# 08_MCU.net
KiCad netlist of a schematic drawn in Altium Designer
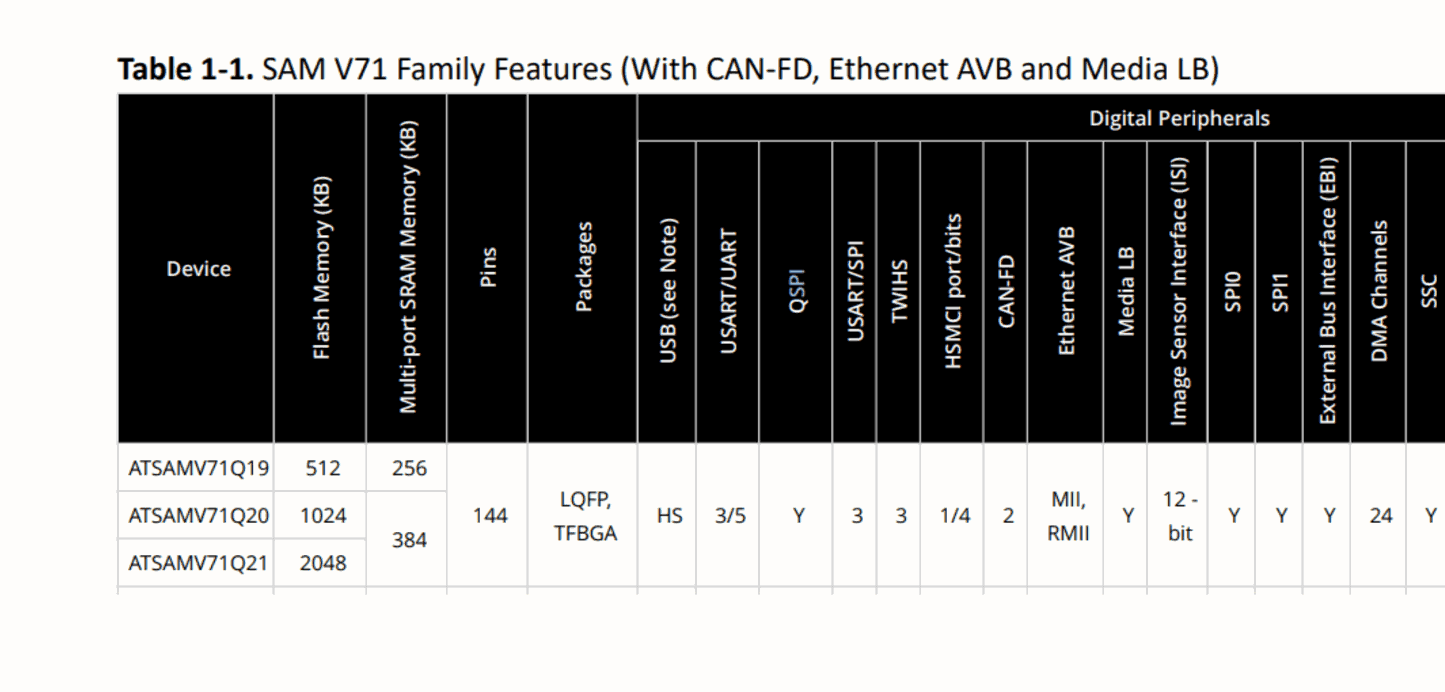
[diagram p0: 08_MCU.SchDoc, top left]
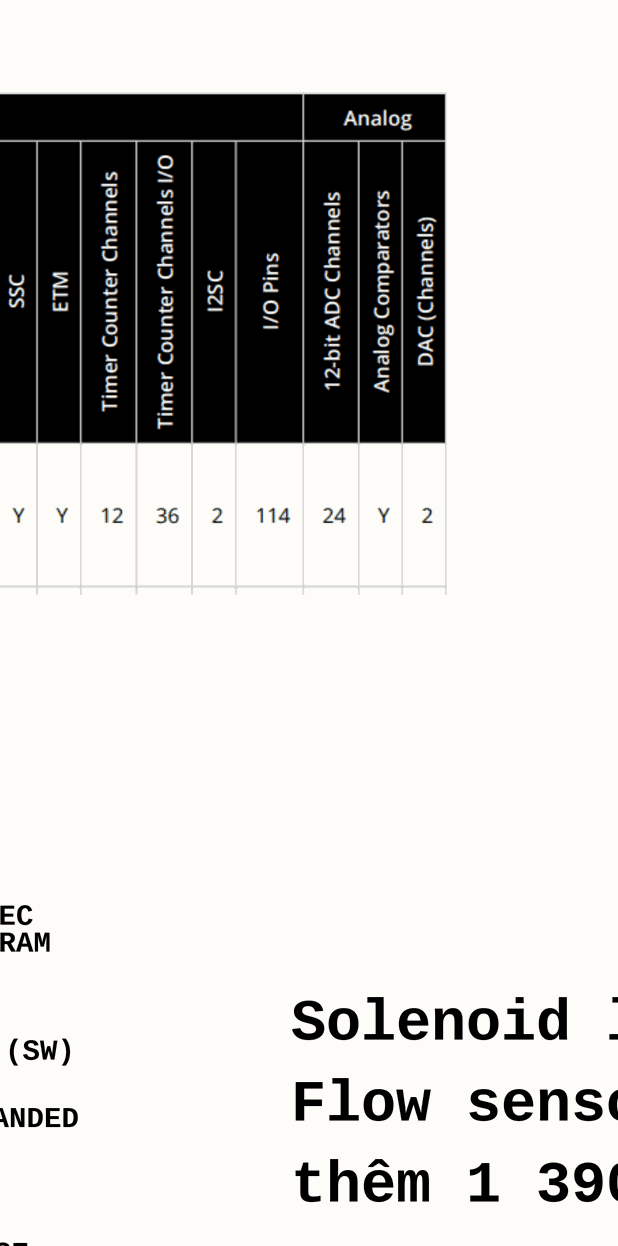
[diagram p1: 08_MCU.SchDoc, top right]
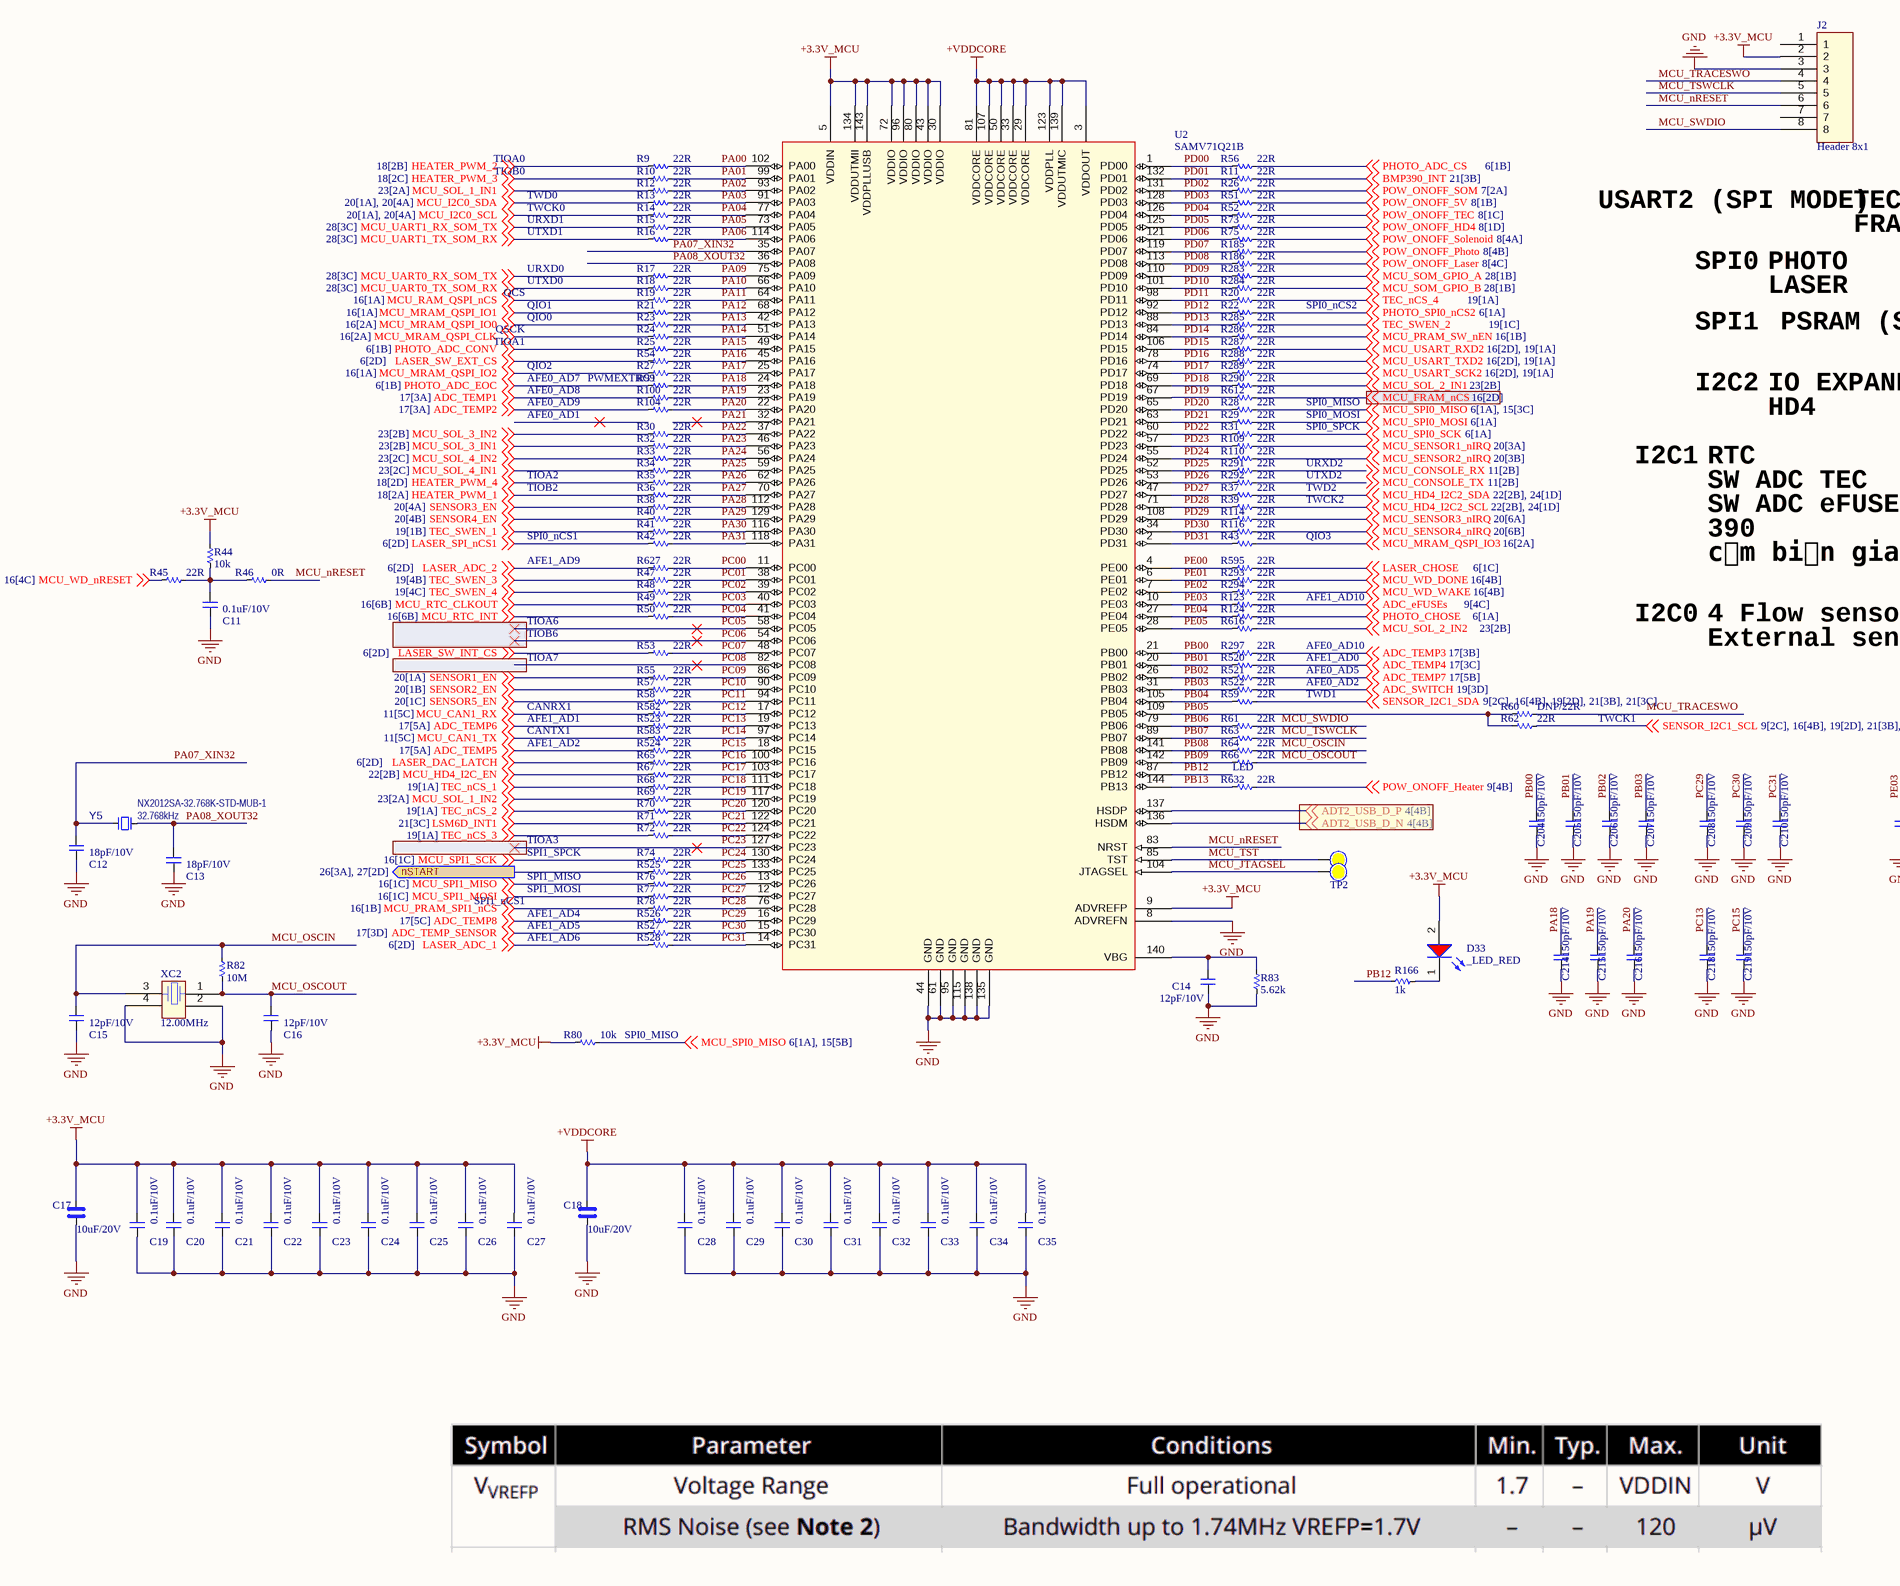
[diagram p2: 08_MCU.SchDoc, bottom left]
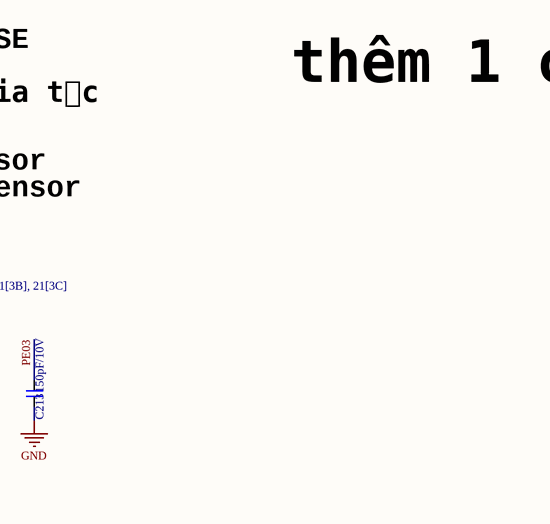
[diagram p3: 08_MCU.SchDoc, bottom right]

(export (version "E")
  (design (tool "Eeschema 10.0.6"))
  (components
    (comp (ref "C11")
      (value "0.1uF/10V")
      (footprint "CAP_C_1005X60")
      (description "CAP CHIP")
      (libsource (lib "LABLIB") (part "_CAP_C_2"))
    )
    (comp (ref "C12")
      (value "18pF/10V")
      (footprint "CAP_C_1005X60")
      (description "CAP CHIP")
      (libsource (lib "LABLIB") (part "_CAP_C_2"))
    )
    (comp (ref "C13")
      (value "18pF/10V")
      (footprint "CAP_C_1005X60")
      (description "CAP CHIP")
      (libsource (lib "LABLIB") (part "_CAP_C_2"))
    )
    (comp (ref "C14")
      (value "12pF/10V")
      (footprint "CAP_C_1005X60")
      (description "CAP CHIP")
      (libsource (lib "LABLIB") (part "_CAP_C_2"))
    )
    (comp (ref "C15")
      (value "12pF/10V")
      (footprint "CAP_C_1005X60")
      (description "CAP CHIP")
      (libsource (lib "LABLIB") (part "_CAP_C_2"))
    )
    (comp (ref "C16")
      (value "12pF/10V")
      (footprint "CAP_C_1005X60")
      (description "CAP CHIP")
      (libsource (lib "LABLIB") (part "_CAP_C_2"))
    )
    (comp (ref "C17")
      (value "10uF/20V")
      (footprint "CAP_C_2012X110")
      (description "CAP CHIP High Value")
      (libsource (lib "LABLIB") (part "_CAP_C_High_2"))
    )
    (comp (ref "C18")
      (value "10uF/20V")
      (footprint "CAP_C_2012X110")
      (description "CAP CHIP High Value")
      (libsource (lib "LABLIB") (part "_CAP_C_High_2"))
    )
    (comp (ref "C19")
      (value "0.1uF/10V")
      (footprint "CAP_C_1005X60")
      (description "CAP CHIP")
      (libsource (lib "LABLIB") (part "_CAP_C_2"))
    )
    (comp (ref "C20")
      (value "0.1uF/10V")
      (footprint "CAP_C_1005X60")
      (description "CAP CHIP")
      (libsource (lib "LABLIB") (part "_CAP_C_2"))
    )
    (comp (ref "C21")
      (value "0.1uF/10V")
      (footprint "CAP_C_1005X60")
      (description "CAP CHIP")
      (libsource (lib "LABLIB") (part "_CAP_C_2"))
    )
    (comp (ref "C22")
      (value "0.1uF/10V")
      (footprint "CAP_C_1005X60")
      (description "CAP CHIP")
      (libsource (lib "LABLIB") (part "_CAP_C_2"))
    )
    (comp (ref "C23")
      (value "0.1uF/10V")
      (footprint "CAP_C_1005X60")
      (description "CAP CHIP")
      (libsource (lib "LABLIB") (part "_CAP_C_2"))
    )
    (comp (ref "C24")
      (value "0.1uF/10V")
      (footprint "CAP_C_1005X60")
      (description "CAP CHIP")
      (libsource (lib "LABLIB") (part "_CAP_C_2"))
    )
    (comp (ref "C25")
      (value "0.1uF/10V")
      (footprint "CAP_C_1005X60")
      (description "CAP CHIP")
      (libsource (lib "LABLIB") (part "_CAP_C_2"))
    )
    (comp (ref "C26")
      (value "0.1uF/10V")
      (footprint "CAP_C_1005X60")
      (description "CAP CHIP")
      (libsource (lib "LABLIB") (part "_CAP_C_2"))
    )
    (comp (ref "C27")
      (value "0.1uF/10V")
      (footprint "CAP_C_1005X60")
      (description "CAP CHIP")
      (libsource (lib "LABLIB") (part "_CAP_C_2"))
    )
    (comp (ref "C28")
      (value "0.1uF/10V")
      (footprint "CAP_C_1005X60")
      (description "CAP CHIP")
      (libsource (lib "LABLIB") (part "_CAP_C_2"))
    )
    (comp (ref "C29")
      (value "0.1uF/10V")
      (footprint "CAP_C_1005X60")
      (description "CAP CHIP")
      (libsource (lib "LABLIB") (part "_CAP_C_2"))
    )
    (comp (ref "C30")
      (value "0.1uF/10V")
      (footprint "CAP_C_1005X60")
      (description "CAP CHIP")
      (libsource (lib "LABLIB") (part "_CAP_C_2"))
    )
    (comp (ref "C31")
      (value "0.1uF/10V")
      (footprint "CAP_C_1005X60")
      (description "CAP CHIP")
      (libsource (lib "LABLIB") (part "_CAP_C_2"))
    )
    (comp (ref "C32")
      (value "0.1uF/10V")
      (footprint "CAP_C_1005X60")
      (description "CAP CHIP")
      (libsource (lib "LABLIB") (part "_CAP_C_2"))
    )
    (comp (ref "C33")
      (value "0.1uF/10V")
      (footprint "CAP_C_1005X60")
      (description "CAP CHIP")
      (libsource (lib "LABLIB") (part "_CAP_C_2"))
    )
    (comp (ref "C34")
      (value "0.1uF/10V")
      (footprint "CAP_C_1005X60")
      (description "CAP CHIP")
      (libsource (lib "LABLIB") (part "_CAP_C_2"))
    )
    (comp (ref "C35")
      (value "0.1uF/10V")
      (footprint "CAP_C_1005X60")
      (description "CAP CHIP")
      (libsource (lib "LABLIB") (part "_CAP_C_2"))
    )
    (comp (ref "C204")
      (value "150pF/10V")
      (footprint "CAP_C_1005X60")
      (description "CAP CHIP")
      (libsource (lib "LABLIB") (part "_CAP_C_2"))
    )
    (comp (ref "C205")
      (value "150pF/10V")
      (footprint "CAP_C_1005X60")
      (description "CAP CHIP")
      (libsource (lib "LABLIB") (part "_CAP_C_2"))
    )
    (comp (ref "C206")
      (value "150pF/10V")
      (footprint "CAP_C_1005X60")
      (description "CAP CHIP")
      (libsource (lib "LABLIB") (part "_CAP_C_2"))
    )
    (comp (ref "C207")
      (value "150pF/10V")
      (footprint "CAP_C_1005X60")
      (description "CAP CHIP")
      (libsource (lib "LABLIB") (part "_CAP_C_2"))
    )
    (comp (ref "C208")
      (value "150pF/10V")
      (footprint "CAP_C_1005X60")
      (description "CAP CHIP")
      (libsource (lib "LABLIB") (part "_CAP_C_2"))
    )
    (comp (ref "C209")
      (value "150pF/10V")
      (footprint "CAP_C_1005X60")
      (description "CAP CHIP")
      (libsource (lib "LABLIB") (part "_CAP_C_2"))
    )
    (comp (ref "C210")
      (value "150pF/10V")
      (footprint "CAP_C_1005X60")
      (description "CAP CHIP")
      (libsource (lib "LABLIB") (part "_CAP_C_2"))
    )
    (comp (ref "C213")
      (value "150pF/10V")
      (footprint "CAP_C_1005X60")
      (description "CAP CHIP")
      (libsource (lib "LABLIB") (part "_CAP_C_2"))
    )
    (comp (ref "C214")
      (value "150pF/10V")
      (footprint "CAP_C_1005X60")
      (description "CAP CHIP")
      (libsource (lib "LABLIB") (part "_CAP_C_2"))
    )
    (comp (ref "C215")
      (value "150pF/10V")
      (footprint "CAP_C_1005X60")
      (description "CAP CHIP")
      (libsource (lib "LABLIB") (part "_CAP_C_2"))
    )
    (comp (ref "C216")
      (value "150pF/10V")
      (footprint "CAP_C_1005X60")
      (description "CAP CHIP")
      (libsource (lib "LABLIB") (part "_CAP_C_2"))
    )
    (comp (ref "C218")
      (value "150pF/10V")
      (footprint "CAP_C_1005X60")
      (description "CAP CHIP")
      (libsource (lib "LABLIB") (part "_CAP_C_2"))
    )
    (comp (ref "C219")
      (value "150pF/10V")
      (footprint "CAP_C_1005X60")
      (description "CAP CHIP")
      (libsource (lib "LABLIB") (part "_CAP_C_2"))
    )
    (comp (ref "D33") (value "_LED_RED") (footprint "LED_0603") (libsource (lib "LABLIB") (part "_LED_RED")))
    (comp (ref "J2")
      (value "Header 8x1")
      (footprint "Header_254P_8x1")
      (libsource (lib "LABLIB") (part "Header 8x1"))
    )
    (comp (ref "R9")
      (value "22R")
      (footprint "RES_C_1005X40")
      (description "RES")
      (libsource (lib "LABLIB") (part "_RES_B_2"))
    )
    (comp (ref "R10")
      (value "22R")
      (footprint "RES_C_1005X40")
      (description "RES")
      (libsource (lib "LABLIB") (part "_RES_B_2"))
    )
    (comp (ref "R11")
      (value "22R")
      (footprint "RES_C_1005X40")
      (description "RES")
      (libsource (lib "LABLIB") (part "_RES_B_2"))
    )
    (comp (ref "R12")
      (value "22R")
      (footprint "RES_C_1005X40")
      (description "RES")
      (libsource (lib "LABLIB") (part "_RES_B_2"))
    )
    (comp (ref "R13")
      (value "22R")
      (footprint "RES_C_1005X40")
      (description "RES")
      (libsource (lib "LABLIB") (part "_RES_B_2"))
    )
    (comp (ref "R14")
      (value "22R")
      (footprint "RES_C_1005X40")
      (description "RES")
      (libsource (lib "LABLIB") (part "_RES_B_2"))
    )
    (comp (ref "R15")
      (value "22R")
      (footprint "RES_C_1005X40")
      (description "RES")
      (libsource (lib "LABLIB") (part "_RES_B_2"))
    )
    (comp (ref "R16")
      (value "22R")
      (footprint "RES_C_1005X40")
      (description "RES")
      (libsource (lib "LABLIB") (part "_RES_B_2"))
    )
    (comp (ref "R17")
      (value "22R")
      (footprint "RES_C_1005X40")
      (description "RES")
      (libsource (lib "LABLIB") (part "_RES_B_2"))
    )
    (comp (ref "R18")
      (value "22R")
      (footprint "RES_C_1005X40")
      (description "RES")
      (libsource (lib "LABLIB") (part "_RES_B_2"))
    )
    (comp (ref "R19")
      (value "22R")
      (footprint "RES_C_1005X40")
      (description "RES")
      (libsource (lib "LABLIB") (part "_RES_B_2"))
    )
    (comp (ref "R20")
      (value "22R")
      (footprint "RES_C_1005X40")
      (description "RES")
      (libsource (lib "LABLIB") (part "_RES_B_2"))
    )
    (comp (ref "R21")
      (value "22R")
      (footprint "RES_C_1005X40")
      (description "RES")
      (libsource (lib "LABLIB") (part "_RES_B_2"))
    )
    (comp (ref "R22")
      (value "22R")
      (footprint "RES_C_1005X40")
      (description "RES")
      (libsource (lib "LABLIB") (part "_RES_B_2"))
    )
    (comp (ref "R23")
      (value "22R")
      (footprint "RES_C_1005X40")
      (description "RES")
      (libsource (lib "LABLIB") (part "_RES_B_2"))
    )
    (comp (ref "R24")
      (value "22R")
      (footprint "RES_C_1005X40")
      (description "RES")
      (libsource (lib "LABLIB") (part "_RES_B_2"))
    )
    (comp (ref "R25")
      (value "22R")
      (footprint "RES_C_1005X40")
      (description "RES")
      (libsource (lib "LABLIB") (part "_RES_B_2"))
    )
    (comp (ref "R26")
      (value "22R")
      (footprint "RES_C_1005X40")
      (description "RES")
      (libsource (lib "LABLIB") (part "_RES_B_2"))
    )
    (comp (ref "R27")
      (value "22R")
      (footprint "RES_C_1005X40")
      (description "RES")
      (libsource (lib "LABLIB") (part "_RES_B_2"))
    )
    (comp (ref "R28")
      (value "22R")
      (footprint "RES_C_1005X40")
      (description "RES")
      (libsource (lib "LABLIB") (part "_RES_B_2"))
    )
    (comp (ref "R29")
      (value "22R")
      (footprint "RES_C_1005X40")
      (description "RES")
      (libsource (lib "LABLIB") (part "_RES_B_2"))
    )
    (comp (ref "R30")
      (value "22R")
      (footprint "RES_C_1005X40")
      (description "RES")
      (libsource (lib "LABLIB") (part "_RES_B_2"))
    )
    (comp (ref "R31")
      (value "22R")
      (footprint "RES_C_1005X40")
      (description "RES")
      (libsource (lib "LABLIB") (part "_RES_B_2"))
    )
    (comp (ref "R32")
      (value "22R")
      (footprint "RES_C_1005X40")
      (description "RES")
      (libsource (lib "LABLIB") (part "_RES_B_2"))
    )
    (comp (ref "R33")
      (value "22R")
      (footprint "RES_C_1005X40")
      (description "RES")
      (libsource (lib "LABLIB") (part "_RES_B_2"))
    )
    (comp (ref "R34")
      (value "22R")
      (footprint "RES_C_1005X40")
      (description "RES")
      (libsource (lib "LABLIB") (part "_RES_B_2"))
    )
    (comp (ref "R35")
      (value "22R")
      (footprint "RES_C_1005X40")
      (description "RES")
      (libsource (lib "LABLIB") (part "_RES_B_2"))
    )
    (comp (ref "R36")
      (value "22R")
      (footprint "RES_C_1005X40")
      (description "RES")
      (libsource (lib "LABLIB") (part "_RES_B_2"))
    )
    (comp (ref "R37")
      (value "22R")
      (footprint "RES_C_1005X40")
      (description "RES")
      (libsource (lib "LABLIB") (part "_RES_B_2"))
    )
    (comp (ref "R38")
      (value "22R")
      (footprint "RES_C_1005X40")
      (description "RES")
      (libsource (lib "LABLIB") (part "_RES_B_2"))
    )
    (comp (ref "R39")
      (value "22R")
      (footprint "RES_C_1005X40")
      (description "RES")
      (libsource (lib "LABLIB") (part "_RES_B_2"))
    )
    (comp (ref "R40")
      (value "22R")
      (footprint "RES_C_1005X40")
      (description "RES")
      (libsource (lib "LABLIB") (part "_RES_B_2"))
    )
    (comp (ref "R41")
      (value "22R")
      (footprint "RES_C_1005X40")
      (description "RES")
      (libsource (lib "LABLIB") (part "_RES_B_2"))
    )
    (comp (ref "R42")
      (value "22R")
      (footprint "RES_C_1005X40")
      (description "RES")
      (libsource (lib "LABLIB") (part "_RES_B_2"))
    )
    (comp (ref "R43")
      (value "22R")
      (footprint "RES_C_1005X40")
      (description "RES")
      (libsource (lib "LABLIB") (part "_RES_B_2"))
    )
    (comp (ref "R44")
      (value "10k")
      (footprint "RES_C_1005X40")
      (description "RES")
      (libsource (lib "LABLIB") (part "_RES_B_2"))
    )
    (comp (ref "R45")
      (value "22R")
      (footprint "RES_C_1005X40")
      (description "RES")
      (libsource (lib "LABLIB") (part "_RES_B_2"))
    )
    (comp (ref "R46")
      (value "0R")
      (footprint "RES_C_1005X40")
      (description "RES")
      (libsource (lib "LABLIB") (part "_RES_B_2"))
    )
    (comp (ref "R47")
      (value "22R")
      (footprint "RES_C_1005X40")
      (description "RES")
      (libsource (lib "LABLIB") (part "_RES_B_2"))
    )
    (comp (ref "R48")
      (value "22R")
      (footprint "RES_C_1005X40")
      (description "RES")
      (libsource (lib "LABLIB") (part "_RES_B_2"))
    )
    (comp (ref "R49")
      (value "22R")
      (footprint "RES_C_1005X40")
      (description "RES")
      (libsource (lib "LABLIB") (part "_RES_B_2"))
    )
    (comp (ref "R50")
      (value "22R")
      (footprint "RES_C_1005X40")
      (description "RES")
      (libsource (lib "LABLIB") (part "_RES_B_2"))
    )
    (comp (ref "R51")
      (value "22R")
      (footprint "RES_C_1005X40")
      (description "RES")
      (libsource (lib "LABLIB") (part "_RES_B_2"))
    )
    (comp (ref "R52")
      (value "22R")
      (footprint "RES_C_1005X40")
      (description "RES")
      (libsource (lib "LABLIB") (part "_RES_B_2"))
    )
    (comp (ref "R53")
      (value "22R")
      (footprint "RES_C_1005X40")
      (description "RES")
      (libsource (lib "LABLIB") (part "_RES_B_2"))
    )
    (comp (ref "R54")
      (value "22R")
      (footprint "RES_C_1005X40")
      (description "RES")
      (libsource (lib "LABLIB") (part "_RES_B_2"))
    )
    (comp (ref "R55")
      (value "22R")
      (footprint "RES_C_1005X40")
      (description "RES")
      (libsource (lib "LABLIB") (part "_RES_B_2"))
    )
    (comp (ref "R56")
      (value "22R")
      (footprint "RES_C_1005X40")
      (description "RES")
      (libsource (lib "LABLIB") (part "_RES_B_2"))
    )
    (comp (ref "R57")
      (value "22R")
      (footprint "RES_C_1005X40")
      (description "RES")
      (libsource (lib "LABLIB") (part "_RES_B_2"))
    )
    (comp (ref "R58")
      (value "22R")
      (footprint "RES_C_1005X40")
      (description "RES")
      (libsource (lib "LABLIB") (part "_RES_B_2"))
    )
    (comp (ref "R59")
      (value "22R")
      (footprint "RES_C_1005X40")
      (description "RES")
      (libsource (lib "LABLIB") (part "_RES_B_2"))
    )
    (comp (ref "R60")
      (value "DNP/22R")
      (footprint "RES_C_1005X40")
      (description "RES")
      (libsource (lib "LABLIB") (part "_RES_B_2"))
    )
    (comp (ref "R61")
      (value "22R")
      (footprint "RES_C_1005X40")
      (description "RES")
      (libsource (lib "LABLIB") (part "_RES_B_2"))
    )
    (comp (ref "R62")
      (value "22R")
      (footprint "RES_C_1005X40")
      (description "RES")
      (libsource (lib "LABLIB") (part "_RES_B_2"))
    )
    (comp (ref "R63")
      (value "22R")
      (footprint "RES_C_1005X40")
      (description "RES")
      (libsource (lib "LABLIB") (part "_RES_B_2"))
    )
    (comp (ref "R64")
      (value "22R")
      (footprint "RES_C_1005X40")
      (description "RES")
      (libsource (lib "LABLIB") (part "_RES_B_2"))
    )
    (comp (ref "R65")
      (value "22R")
      (footprint "RES_C_1005X40")
      (description "RES")
      (libsource (lib "LABLIB") (part "_RES_B_2"))
    )
    (comp (ref "R66")
      (value "22R")
      (footprint "RES_C_1005X40")
      (description "RES")
      (libsource (lib "LABLIB") (part "_RES_B_2"))
    )
    (comp (ref "R67")
      (value "22R")
      (footprint "RES_C_1005X40")
      (description "RES")
      (libsource (lib "LABLIB") (part "_RES_B_2"))
    )
    (comp (ref "R68")
      (value "22R")
      (footprint "RES_C_1005X40")
      (description "RES")
      (libsource (lib "LABLIB") (part "_RES_B_2"))
    )
    (comp (ref "R69")
      (value "22R")
      (footprint "RES_C_1005X40")
      (description "RES")
      (libsource (lib "LABLIB") (part "_RES_B_2"))
    )
    (comp (ref "R70")
      (value "22R")
      (footprint "RES_C_1005X40")
      (description "RES")
      (libsource (lib "LABLIB") (part "_RES_B_2"))
    )
    (comp (ref "R71")
      (value "22R")
      (footprint "RES_C_1005X40")
      (description "RES")
      (libsource (lib "LABLIB") (part "_RES_B_2"))
    )
    (comp (ref "R72")
      (value "22R")
      (footprint "RES_C_1005X40")
      (description "RES")
      (libsource (lib "LABLIB") (part "_RES_B_2"))
    )
    (comp (ref "R73")
      (value "22R")
      (footprint "RES_C_1005X40")
      (description "RES")
      (libsource (lib "LABLIB") (part "_RES_B_2"))
    )
    (comp (ref "R74")
      (value "22R")
      (footprint "RES_C_1005X40")
      (description "RES")
      (libsource (lib "LABLIB") (part "_RES_B_2"))
    )
    (comp (ref "R75")
      (value "22R")
      (footprint "RES_C_1005X40")
      (description "RES")
      (libsource (lib "LABLIB") (part "_RES_B_2"))
    )
    (comp (ref "R76")
      (value "22R")
      (footprint "RES_C_1005X40")
      (description "RES")
      (libsource (lib "LABLIB") (part "_RES_B_2"))
    )
    (comp (ref "R77")
      (value "22R")
      (footprint "RES_C_1005X40")
      (description "RES")
      (libsource (lib "LABLIB") (part "_RES_B_2"))
    )
    (comp (ref "R78")
      (value "22R")
      (footprint "RES_C_1005X40")
      (description "RES")
      (libsource (lib "LABLIB") (part "_RES_B_2"))
    )
    (comp (ref "R80")
      (value "10k")
      (footprint "RES_C_1005X40")
      (description "RES")
      (libsource (lib "LABLIB") (part "_RES_B_2"))
    )
    (comp (ref "R82")
      (value "10M")
      (footprint "RES_C_1005X40")
      (description "RES")
      (libsource (lib "LABLIB") (part "_RES_B_2"))
    )
    (comp (ref "R83")
      (value "5.62k")
      (footprint "RES_C_1005X40")
      (description "RES")
      (libsource (lib "LABLIB") (part "_RES_B_2"))
    )
    (comp (ref "R99")
      (value "22R")
      (footprint "RES_C_1005X40")
      (description "RES")
      (libsource (lib "LABLIB") (part "_RES_B_2"))
    )
    (comp (ref "R100")
      (value "22R")
      (footprint "RES_C_1005X40")
      (description "RES")
      (libsource (lib "LABLIB") (part "_RES_B_2"))
    )
    (comp (ref "R104")
      (value "22R")
      (footprint "RES_C_1005X40")
      (description "RES")
      (libsource (lib "LABLIB") (part "_RES_B_2"))
    )
    (comp (ref "R109")
      (value "22R")
      (footprint "RES_C_1005X40")
      (description "RES")
      (libsource (lib "LABLIB") (part "_RES_B_2"))
    )
    (comp (ref "R110")
      (value "22R")
      (footprint "RES_C_1005X40")
      (description "RES")
      (libsource (lib "LABLIB") (part "_RES_B_2"))
    )
    (comp (ref "R114")
      (value "22R")
      (footprint "RES_C_1005X40")
      (description "RES")
      (libsource (lib "LABLIB") (part "_RES_B_2"))
    )
    (comp (ref "R116")
      (value "22R")
      (footprint "RES_C_1005X40")
      (description "RES")
      (libsource (lib "LABLIB") (part "_RES_B_2"))
    )
    (comp (ref "R123")
      (value "22R")
      (footprint "RES_C_1005X40")
      (description "RES")
      (libsource (lib "LABLIB") (part "_RES_B_2"))
    )
    (comp (ref "R124")
      (value "22R")
      (footprint "RES_C_1005X40")
      (description "RES")
      (libsource (lib "LABLIB") (part "_RES_B_2"))
    )
    (comp (ref "R166")
      (value "1k")
      (footprint "RES_C_1005X40")
      (description "RES")
      (libsource (lib "LABLIB") (part "_RES_B_2"))
    )
    (comp (ref "R185")
      (value "22R")
      (footprint "RES_C_1005X40")
      (description "RES")
      (libsource (lib "LABLIB") (part "_RES_B_2"))
    )
    (comp (ref "R186")
      (value "22R")
      (footprint "RES_C_1005X40")
      (description "RES")
      (libsource (lib "LABLIB") (part "_RES_B_2"))
    )
    (comp (ref "R283")
      (value "22R")
      (footprint "RES_C_1005X40")
      (description "RES")
      (libsource (lib "LABLIB") (part "_RES_B_2"))
    )
    (comp (ref "R284")
      (value "22R")
      (footprint "RES_C_1005X40")
      (description "RES")
      (libsource (lib "LABLIB") (part "_RES_B_2"))
    )
    (comp (ref "R285")
      (value "22R")
      (footprint "RES_C_1005X40")
      (description "RES")
      (libsource (lib "LABLIB") (part "_RES_B_2"))
    )
    (comp (ref "R286")
      (value "22R")
      (footprint "RES_C_1005X40")
      (description "RES")
      (libsource (lib "LABLIB") (part "_RES_B_2"))
    )
    (comp (ref "R287")
      (value "22R")
      (footprint "RES_C_1005X40")
      (description "RES")
      (libsource (lib "LABLIB") (part "_RES_B_2"))
    )
    (comp (ref "R288")
      (value "22R")
      (footprint "RES_C_1005X40")
      (description "RES")
      (libsource (lib "LABLIB") (part "_RES_B_2"))
    )
    (comp (ref "R289")
      (value "22R")
      (footprint "RES_C_1005X40")
      (description "RES")
      (libsource (lib "LABLIB") (part "_RES_B_2"))
    )
    (comp (ref "R290")
      (value "22R")
      (footprint "RES_C_1005X40")
      (description "RES")
      (libsource (lib "LABLIB") (part "_RES_B_2"))
    )
    (comp (ref "R291")
      (value "22R")
      (footprint "RES_C_1005X40")
      (description "RES")
      (libsource (lib "LABLIB") (part "_RES_B_2"))
    )
    (comp (ref "R292")
      (value "22R")
      (footprint "RES_C_1005X40")
      (description "RES")
      (libsource (lib "LABLIB") (part "_RES_B_2"))
    )
    (comp (ref "R293")
      (value "22R")
      (footprint "RES_C_1005X40")
      (description "RES")
      (libsource (lib "LABLIB") (part "_RES_B_2"))
    )
    (comp (ref "R294")
      (value "22R")
      (footprint "RES_C_1005X40")
      (description "RES")
      (libsource (lib "LABLIB") (part "_RES_B_2"))
    )
    (comp (ref "R297")
      (value "22R")
      (footprint "RES_C_1005X40")
      (description "RES")
      (libsource (lib "LABLIB") (part "_RES_B_2"))
    )
    (comp (ref "R520")
      (value "22R")
      (footprint "RES_C_1005X40")
      (description "RES")
      (libsource (lib "LABLIB") (part "_RES_B_2"))
    )
    (comp (ref "R521")
      (value "22R")
      (footprint "RES_C_1005X40")
      (description "RES")
      (libsource (lib "LABLIB") (part "_RES_B_2"))
    )
    (comp (ref "R522")
      (value "22R")
      (footprint "RES_C_1005X40")
      (description "RES")
      (libsource (lib "LABLIB") (part "_RES_B_2"))
    )
    (comp (ref "R523")
      (value "22R")
      (footprint "RES_C_1005X40")
      (description "RES")
      (libsource (lib "LABLIB") (part "_RES_B_2"))
    )
    (comp (ref "R524")
      (value "22R")
      (footprint "RES_C_1005X40")
      (description "RES")
      (libsource (lib "LABLIB") (part "_RES_B_2"))
    )
    (comp (ref "R525")
      (value "22R")
      (footprint "RES_C_1005X40")
      (description "RES")
      (libsource (lib "LABLIB") (part "_RES_B_2"))
    )
    (comp (ref "R526")
      (value "22R")
      (footprint "RES_C_1005X40")
      (description "RES")
      (libsource (lib "LABLIB") (part "_RES_B_2"))
    )
    (comp (ref "R527")
      (value "22R")
      (footprint "RES_C_1005X40")
      (description "RES")
      (libsource (lib "LABLIB") (part "_RES_B_2"))
    )
    (comp (ref "R528")
      (value "22R")
      (footprint "RES_C_1005X40")
      (description "RES")
      (libsource (lib "LABLIB") (part "_RES_B_2"))
    )
    (comp (ref "R582")
      (value "22R")
      (footprint "RES_C_1005X40")
      (description "RES")
      (libsource (lib "LABLIB") (part "_RES_B_2"))
    )
    (comp (ref "R583")
      (value "22R")
      (footprint "RES_C_1005X40")
      (description "RES")
      (libsource (lib "LABLIB") (part "_RES_B_2"))
    )
    (comp (ref "R595")
      (value "22R")
      (footprint "RES_C_1005X40")
      (description "RES")
      (libsource (lib "LABLIB") (part "_RES_B_2"))
    )
    (comp (ref "R612")
      (value "22R")
      (footprint "RES_C_1005X40")
      (description "RES")
      (libsource (lib "LABLIB") (part "_RES_B_2"))
    )
    (comp (ref "R616")
      (value "22R")
      (footprint "RES_C_1005X40")
      (description "RES")
      (libsource (lib "LABLIB") (part "_RES_B_2"))
    )
    (comp (ref "R627")
      (value "22R")
      (footprint "RES_C_1005X40")
      (description "RES")
      (libsource (lib "LABLIB") (part "_RES_B_2"))
    )
    (comp (ref "R632")
      (value "22R")
      (footprint "RES_C_1005X40")
      (description "RES")
      (libsource (lib "LABLIB") (part "_RES_B_2"))
    )
    (comp (ref "TP1")
      (value "~")
      (footprint "Testpoint_TH_D130H80")
      (description "Test Point")
      (libsource (lib "LABLIB") (part "Test Point"))
    )
    (comp (ref "TP2")
      (value "~")
      (footprint "Testpoint_TH_D130H80")
      (description "Test Point")
      (libsource (lib "LABLIB") (part "Test Point"))
    )
    (comp (ref "U2")
      (value "SAMV71Q21B")
      (footprint "AP6-00118")
      (description "SAM 32-bit ARM Cortex-M* RISC MCU, SAMV71B Series, QFP144")
      (fields (field (name "MANUFACTURER") "MICROCHIP") (field (name "MPN") "ATSAMV71Q21B-AAB"))
      (libsource (lib "AltiumDbLib") (part "SAMV7_LQFP144"))
    )
    (comp (ref "XC2")
      (value "12.00MHz")
      (footprint "AP7-00039")
      (description "Fox FQ5032B 12.0MHz SMD crystal 738B-12")
      (fields (field (name "TOLERANCE") "Â±30ppm") (field (name "MANUFACTURER") "Fox  Electronics"))
      (libsource (lib "AltiumDbLib") (part "CRYSTAL1324"))
    )
    (comp (ref "Y5")
      (value "32.768kHz")
      (footprint "CRYSTAL_NX2012SA")
      (description "Crystal")
      (fields
        (field (name "TOLERANCE") "±20ppm")
        (field (name "MANUFACTURER PART NUMBER 1") "NX2012SA-32.768K-STD-MUB-1")
        (field (name "Comment") "Crystal 2 Pins")
        (field (name "OWNER") "Jamus Griego")
      )
      (libsource (lib "MCHP-CDB") (part "Crystal 2 Pins"))
    )
  )
  (nets
    (net (code "1") (name "+3.3V_MCU") (class "Default")
      (node (ref "C17") (pin "1") (pinfunction "1_1") (pintype "passive"))
      (node (ref "C19") (pin "2") (pinfunction "2_2") (pintype "passive"))
      (node (ref "C20") (pin "2") (pinfunction "2_2") (pintype "passive"))
      (node (ref "C21") (pin "2") (pinfunction "2_2") (pintype "passive"))
      (node (ref "C22") (pin "2") (pinfunction "2_2") (pintype "passive"))
      (node (ref "C23") (pin "2") (pinfunction "2_2") (pintype "passive"))
      (node (ref "C24") (pin "2") (pinfunction "2_2") (pintype "passive"))
      (node (ref "C25") (pin "2") (pinfunction "2_2") (pintype "passive"))
      (node (ref "C26") (pin "2") (pinfunction "2_2") (pintype "passive"))
      (node (ref "C27") (pin "2") (pinfunction "2_2") (pintype "passive"))
      (node (ref "D33") (pin "2") (pinfunction "A_2") (pintype "passive"))
      (node (ref "J2") (pin "2") (pinfunction "2_2") (pintype "passive"))
      (node (ref "R44") (pin "2") (pinfunction "2_2") (pintype "passive"))
      (node (ref "R80") (pin "2") (pinfunction "2_2") (pintype "passive"))
      (node (ref "U2") (pin "134") (pinfunction "VDDUTMII_134") (pintype "power_in"))
      (node (ref "U2") (pin "143") (pinfunction "VDDPLLUSB_143") (pintype "power_in"))
      (node (ref "U2") (pin "30") (pinfunction "VDDIO_30") (pintype "power_in"))
      (node (ref "U2") (pin "43") (pinfunction "VDDIO_43") (pintype "power_in"))
      (node (ref "U2") (pin "5") (pinfunction "VDDIN_5") (pintype "power_in"))
      (node (ref "U2") (pin "72") (pinfunction "VDDIO_72") (pintype "power_in"))
      (node (ref "U2") (pin "80") (pinfunction "VDDIO_80") (pintype "power_in"))
      (node (ref "U2") (pin "9") (pinfunction "ADVREFP_9") (pintype "power_in"))
      (node (ref "U2") (pin "96") (pinfunction "VDDIO_96") (pintype "power_in"))
    )
    (net (code "2") (name "+VDDCORE") (class "Default")
      (node (ref "C18") (pin "1") (pinfunction "1_1") (pintype "passive"))
      (node (ref "C28") (pin "2") (pinfunction "2_2") (pintype "passive"))
      (node (ref "C29") (pin "2") (pinfunction "2_2") (pintype "passive"))
      (node (ref "C30") (pin "2") (pinfunction "2_2") (pintype "passive"))
      (node (ref "C31") (pin "2") (pinfunction "2_2") (pintype "passive"))
      (node (ref "C32") (pin "2") (pinfunction "2_2") (pintype "passive"))
      (node (ref "C33") (pin "2") (pinfunction "2_2") (pintype "passive"))
      (node (ref "C34") (pin "2") (pinfunction "2_2") (pintype "passive"))
      (node (ref "C35") (pin "2") (pinfunction "2_2") (pintype "passive"))
      (node (ref "U2") (pin "107") (pinfunction "VDDCORE_107") (pintype "power_in"))
      (node (ref "U2") (pin "123") (pinfunction "VDDPLL_123") (pintype "power_in"))
      (node (ref "U2") (pin "139") (pinfunction "VDDUTMIC_139") (pintype "power_in"))
      (node (ref "U2") (pin "29") (pinfunction "VDDCORE_29") (pintype "power_in"))
      (node (ref "U2") (pin "3") (pinfunction "VDDOUT_3") (pintype "power_in"))
      (node (ref "U2") (pin "33") (pinfunction "VDDCORE_33") (pintype "power_in"))
      (node (ref "U2") (pin "50") (pinfunction "VDDCORE_50") (pintype "power_in"))
      (node (ref "U2") (pin "81") (pinfunction "VDDCORE_81") (pintype "power_in"))
    )
    (net (code "3") (name "/MCU_JTAGSEL") (class "Default")
      (node (ref "TP2") (pin "1") (pinfunction "1_1") (pintype "passive"))
      (node (ref "U2") (pin "104") (pinfunction "JTAGSEL_104") (pintype "input"))
    )
    (net (code "4") (name "/MCU_OSCIN") (class "Default")
      (node (ref "C15") (pin "2") (pinfunction "2_2") (pintype "passive"))
      (node (ref "R64") (pin "1") (pinfunction "1_1") (pintype "passive"))
      (node (ref "R82") (pin "2") (pinfunction "2_2") (pintype "passive"))
      (node (ref "XC2") (pin "3") (pinfunction "3_3") (pintype "passive"))
    )
    (net (code "5") (name "/MCU_OSCOUT") (class "Default")
      (node (ref "C16") (pin "2") (pinfunction "2_2") (pintype "passive"))
      (node (ref "R66") (pin "1") (pinfunction "1_1") (pintype "passive"))
      (node (ref "R82") (pin "1") (pinfunction "1_1") (pintype "passive"))
      (node (ref "XC2") (pin "1") (pinfunction "1_1") (pintype "passive"))
    )
    (net (code "6") (name "/MCU_SWDIO") (class "Default")
      (node (ref "J2") (pin "8") (pinfunction "8_8") (pintype "passive"))
      (node (ref "R61") (pin "1") (pinfunction "1_1") (pintype "passive"))
    )
    (net (code "7") (name "/MCU_TRACESWO") (class "Default")
      (node (ref "J2") (pin "4") (pinfunction "4_4") (pintype "passive"))
      (node (ref "R60") (pin "1") (pinfunction "1_1") (pintype "passive"))
    )
    (net (code "8") (name "/MCU_TST") (class "Default")
      (node (ref "TP1") (pin "1") (pinfunction "1_1") (pintype "passive"))
      (node (ref "U2") (pin "85") (pinfunction "TST_85") (pintype "input"))
    )
    (net (code "9") (name "/MCU_TSWCLK") (class "Default")
      (node (ref "J2") (pin "5") (pinfunction "5_5") (pintype "passive"))
      (node (ref "R63") (pin "1") (pinfunction "1_1") (pintype "passive"))
    )
    (net (code "10") (name "/MCU_nRESET") (class "Default")
      (node (ref "J2") (pin "6") (pinfunction "6_6") (pintype "passive"))
      (node (ref "R46") (pin "1") (pinfunction "1_1") (pintype "passive"))
      (node (ref "U2") (pin "83") (pinfunction "NRST_83") (pintype "input"))
    )
    (net (code "11") (name "/PA00") (class "Default")
      (node (ref "R9") (pin "1") (pinfunction "1_1") (pintype "passive"))
      (node (ref "U2") (pin "102") (pinfunction "PA00_102") (pintype "bidirectional"))
    )
    (net (code "12") (name "/PA01") (class "Default")
      (node (ref "R10") (pin "1") (pinfunction "1_1") (pintype "passive"))
      (node (ref "U2") (pin "99") (pinfunction "PA01_99") (pintype "bidirectional"))
    )
    (net (code "13") (name "/PA02") (class "Default")
      (node (ref "R12") (pin "1") (pinfunction "1_1") (pintype "passive"))
      (node (ref "U2") (pin "93") (pinfunction "PA02_93") (pintype "bidirectional"))
    )
    (net (code "14") (name "/PA03") (class "Default")
      (node (ref "R13") (pin "1") (pinfunction "1_1") (pintype "passive"))
      (node (ref "U2") (pin "91") (pinfunction "PA03_91") (pintype "bidirectional"))
    )
    (net (code "15") (name "/PA04") (class "Default")
      (node (ref "R14") (pin "1") (pinfunction "1_1") (pintype "passive"))
      (node (ref "U2") (pin "77") (pinfunction "PA04_77") (pintype "bidirectional"))
    )
    (net (code "16") (name "/PA05") (class "Default")
      (node (ref "R15") (pin "1") (pinfunction "1_1") (pintype "passive"))
      (node (ref "U2") (pin "73") (pinfunction "PA05_73") (pintype "bidirectional"))
    )
    (net (code "17") (name "/PA06") (class "Default")
      (node (ref "R16") (pin "1") (pinfunction "1_1") (pintype "passive"))
      (node (ref "U2") (pin "114") (pinfunction "PA06_114") (pintype "bidirectional"))
    )
    (net (code "18") (name "/PA07_XIN32") (class "Default")
      (node (ref "C12") (pin "2") (pinfunction "2_2") (pintype "passive"))
      (node (ref "U2") (pin "35") (pinfunction "PA07_35") (pintype "bidirectional"))
      (node (ref "Y5") (pin "2") (pinfunction "Osc2_2") (pintype "passive"))
    )
    (net (code "19") (name "/PA08_XOUT32") (class "Default")
      (node (ref "C13") (pin "2") (pinfunction "2_2") (pintype "passive"))
      (node (ref "U2") (pin "36") (pinfunction "PA08_36") (pintype "bidirectional"))
      (node (ref "Y5") (pin "1") (pinfunction "Osc1_1") (pintype "passive"))
    )
    (net (code "20") (name "/PA09") (class "Default")
      (node (ref "R17") (pin "1") (pinfunction "1_1") (pintype "passive"))
      (node (ref "U2") (pin "75") (pinfunction "PA09_75") (pintype "bidirectional"))
    )
    (net (code "21") (name "/PA10") (class "Default")
      (node (ref "R18") (pin "1") (pinfunction "1_1") (pintype "passive"))
      (node (ref "U2") (pin "66") (pinfunction "PA10_66") (pintype "bidirectional"))
    )
    (net (code "22") (name "/PA11") (class "Default")
      (node (ref "R19") (pin "1") (pinfunction "1_1") (pintype "passive"))
      (node (ref "U2") (pin "64") (pinfunction "PA11_64") (pintype "bidirectional"))
    )
    (net (code "23") (name "/PA12") (class "Default")
      (node (ref "R21") (pin "1") (pinfunction "1_1") (pintype "passive"))
      (node (ref "U2") (pin "68") (pinfunction "PA12_68") (pintype "bidirectional"))
    )
    (net (code "24") (name "/PA13") (class "Default")
      (node (ref "R23") (pin "1") (pinfunction "1_1") (pintype "passive"))
      (node (ref "U2") (pin "42") (pinfunction "PA13_42") (pintype "bidirectional"))
    )
    (net (code "25") (name "/PA14") (class "Default")
      (node (ref "R24") (pin "1") (pinfunction "1_1") (pintype "passive"))
      (node (ref "U2") (pin "51") (pinfunction "PA14_51") (pintype "bidirectional"))
    )
    (net (code "26") (name "/PA15") (class "Default")
      (node (ref "R25") (pin "1") (pinfunction "1_1") (pintype "passive"))
      (node (ref "U2") (pin "49") (pinfunction "PA15_49") (pintype "bidirectional"))
    )
    (net (code "27") (name "/PA16") (class "Default")
      (node (ref "R54") (pin "1") (pinfunction "1_1") (pintype "passive"))
      (node (ref "U2") (pin "45") (pinfunction "PA16_45") (pintype "bidirectional"))
    )
    (net (code "28") (name "/PA17") (class "Default")
      (node (ref "R27") (pin "1") (pinfunction "1_1") (pintype "passive"))
      (node (ref "U2") (pin "25") (pinfunction "PA17_25") (pintype "bidirectional"))
    )
    (net (code "29") (name "/PA18") (class "Default")
      (node (ref "C214") (pin "2") (pinfunction "2_2") (pintype "passive"))
      (node (ref "R99") (pin "1") (pinfunction "1_1") (pintype "passive"))
      (node (ref "U2") (pin "24") (pinfunction "PA18_24") (pintype "bidirectional"))
    )
    (net (code "30") (name "/PA19") (class "Default")
      (node (ref "C215") (pin "2") (pinfunction "2_2") (pintype "passive"))
      (node (ref "R100") (pin "1") (pinfunction "1_1") (pintype "passive"))
      (node (ref "U2") (pin "23") (pinfunction "PA19_23") (pintype "bidirectional"))
    )
    (net (code "31") (name "/PA20") (class "Default")
      (node (ref "C216") (pin "2") (pinfunction "2_2") (pintype "passive"))
      (node (ref "R104") (pin "1") (pinfunction "1_1") (pintype "passive"))
      (node (ref "U2") (pin "22") (pinfunction "PA20_22") (pintype "bidirectional"))
    )
    (net (code "32") (name "/PA21") (class "Default")
      (node (ref "U2") (pin "32") (pinfunction "PA21_32") (pintype "bidirectional"))
    )
    (net (code "33") (name "/PA22") (class "Default")
      (node (ref "R30") (pin "1") (pinfunction "1_1") (pintype "passive"))
      (node (ref "U2") (pin "37") (pinfunction "PA22_37") (pintype "bidirectional"))
    )
    (net (code "34") (name "/PA23") (class "Default")
      (node (ref "R32") (pin "1") (pinfunction "1_1") (pintype "passive"))
      (node (ref "U2") (pin "46") (pinfunction "PA23_46") (pintype "bidirectional"))
    )
    (net (code "35") (name "/PA24") (class "Default")
      (node (ref "R33") (pin "1") (pinfunction "1_1") (pintype "passive"))
      (node (ref "U2") (pin "56") (pinfunction "PA24_56") (pintype "bidirectional"))
    )
    (net (code "36") (name "/PA25") (class "Default")
      (node (ref "R34") (pin "1") (pinfunction "1_1") (pintype "passive"))
      (node (ref "U2") (pin "59") (pinfunction "PA25_59") (pintype "bidirectional"))
    )
    (net (code "37") (name "/PA26") (class "Default")
      (node (ref "R35") (pin "1") (pinfunction "1_1") (pintype "passive"))
      (node (ref "U2") (pin "62") (pinfunction "PA26_62") (pintype "bidirectional"))
    )
    (net (code "38") (name "/PA27") (class "Default")
      (node (ref "R36") (pin "1") (pinfunction "1_1") (pintype "passive"))
      (node (ref "U2") (pin "70") (pinfunction "PA27_70") (pintype "bidirectional"))
    )
    (net (code "39") (name "/PA28") (class "Default")
      (node (ref "R38") (pin "1") (pinfunction "1_1") (pintype "passive"))
      (node (ref "U2") (pin "112") (pinfunction "PA28_112") (pintype "bidirectional"))
    )
    (net (code "40") (name "/PA29") (class "Default")
      (node (ref "R40") (pin "1") (pinfunction "1_1") (pintype "passive"))
      (node (ref "U2") (pin "129") (pinfunction "PA29_129") (pintype "bidirectional"))
    )
    (net (code "41") (name "/PA30") (class "Default")
      (node (ref "R41") (pin "1") (pinfunction "1_1") (pintype "passive"))
      (node (ref "U2") (pin "116") (pinfunction "PA30_116") (pintype "bidirectional"))
    )
    (net (code "42") (name "/PA31") (class "Default")
      (node (ref "R42") (pin "1") (pinfunction "1_1") (pintype "passive"))
      (node (ref "U2") (pin "118") (pinfunction "PA31_118") (pintype "bidirectional"))
    )
    (net (code "43") (name "/PB00") (class "Default")
      (node (ref "C204") (pin "2") (pinfunction "2_2") (pintype "passive"))
      (node (ref "R297") (pin "2") (pinfunction "2_2") (pintype "passive"))
      (node (ref "U2") (pin "21") (pinfunction "PB00_21") (pintype "bidirectional"))
    )
    (net (code "44") (name "/PB01") (class "Default")
      (node (ref "C205") (pin "2") (pinfunction "2_2") (pintype "passive"))
      (node (ref "R520") (pin "2") (pinfunction "2_2") (pintype "passive"))
      (node (ref "U2") (pin "20") (pinfunction "PB01_20") (pintype "bidirectional"))
    )
    (net (code "45") (name "/PB02") (class "Default")
      (node (ref "C206") (pin "2") (pinfunction "2_2") (pintype "passive"))
      (node (ref "R521") (pin "2") (pinfunction "2_2") (pintype "passive"))
      (node (ref "U2") (pin "26") (pinfunction "PB02_26") (pintype "bidirectional"))
    )
    (net (code "46") (name "/PB03") (class "Default")
      (node (ref "C207") (pin "2") (pinfunction "2_2") (pintype "passive"))
      (node (ref "R522") (pin "2") (pinfunction "2_2") (pintype "passive"))
      (node (ref "U2") (pin "31") (pinfunction "PB03_31") (pintype "bidirectional"))
    )
    (net (code "47") (name "/PB04") (class "Default")
      (node (ref "R59") (pin "2") (pinfunction "2_2") (pintype "passive"))
      (node (ref "U2") (pin "105") (pinfunction "PB04_105") (pintype "bidirectional"))
    )
    (net (code "48") (name "/PB05") (class "Default")
      (node (ref "R60") (pin "2") (pinfunction "2_2") (pintype "passive"))
      (node (ref "R62") (pin "2") (pinfunction "2_2") (pintype "passive"))
      (node (ref "U2") (pin "109") (pinfunction "PB05_109") (pintype "bidirectional"))
    )
    (net (code "49") (name "/PB06") (class "Default")
      (node (ref "R61") (pin "2") (pinfunction "2_2") (pintype "passive"))
      (node (ref "U2") (pin "79") (pinfunction "PB06_79") (pintype "bidirectional"))
    )
    (net (code "50") (name "/PB07") (class "Default")
      (node (ref "R63") (pin "2") (pinfunction "2_2") (pintype "passive"))
      (node (ref "U2") (pin "89") (pinfunction "PB07_89") (pintype "bidirectional"))
    )
    (net (code "51") (name "/PB08") (class "Default")
      (node (ref "R64") (pin "2") (pinfunction "2_2") (pintype "passive"))
      (node (ref "U2") (pin "141") (pinfunction "PB08_141") (pintype "bidirectional"))
    )
    (net (code "52") (name "/PB09") (class "Default")
      (node (ref "R66") (pin "2") (pinfunction "2_2") (pintype "passive"))
      (node (ref "U2") (pin "142") (pinfunction "PB09_142") (pintype "bidirectional"))
    )
    (net (code "53") (name "/PB12") (class "Default")
      (node (ref "R166") (pin "1") (pinfunction "1_1") (pintype "passive"))
      (node (ref "U2") (pin "87") (pinfunction "PB12_87") (pintype "bidirectional"))
    )
    (net (code "54") (name "/PB13") (class "Default")
      (node (ref "R632") (pin "2") (pinfunction "2_2") (pintype "passive"))
      (node (ref "U2") (pin "144") (pinfunction "PB13_144") (pintype "bidirectional"))
    )
    (net (code "55") (name "/PC00") (class "Default")
      (node (ref "R627") (pin "1") (pinfunction "1_1") (pintype "passive"))
      (node (ref "U2") (pin "11") (pinfunction "PC00_11") (pintype "bidirectional"))
    )
    (net (code "56") (name "/PC01") (class "Default")
      (node (ref "R47") (pin "1") (pinfunction "1_1") (pintype "passive"))
      (node (ref "U2") (pin "38") (pinfunction "PC01_38") (pintype "bidirectional"))
    )
    (net (code "57") (name "/PC02") (class "Default")
      (node (ref "R48") (pin "1") (pinfunction "1_1") (pintype "passive"))
      (node (ref "U2") (pin "39") (pinfunction "PC02_39") (pintype "bidirectional"))
    )
    (net (code "58") (name "/PC03") (class "Default")
      (node (ref "R49") (pin "1") (pinfunction "1_1") (pintype "passive"))
      (node (ref "U2") (pin "40") (pinfunction "PC03_40") (pintype "bidirectional"))
    )
    (net (code "59") (name "/PC04") (class "Default")
      (node (ref "R50") (pin "1") (pinfunction "1_1") (pintype "passive"))
      (node (ref "U2") (pin "41") (pinfunction "PC04_41") (pintype "bidirectional"))
    )
    (net (code "60") (name "/PC05") (class "Default")
      (node (ref "U2") (pin "58") (pinfunction "PC05_58") (pintype "bidirectional+no_connect"))
    )
    (net (code "61") (name "/PC06") (class "Default")
      (node (ref "U2") (pin "54") (pinfunction "PC06_54") (pintype "bidirectional+no_connect"))
    )
    (net (code "62") (name "/PC07") (class "Default")
      (node (ref "R53") (pin "1") (pinfunction "1_1") (pintype "passive"))
      (node (ref "U2") (pin "48") (pinfunction "PC07_48") (pintype "bidirectional"))
    )
    (net (code "63") (name "/PC08") (class "Default")
      (node (ref "U2") (pin "82") (pinfunction "PC08_82") (pintype "bidirectional"))
    )
    (net (code "64") (name "/PC09") (class "Default")
      (node (ref "R55") (pin "1") (pinfunction "1_1") (pintype "passive"))
      (node (ref "U2") (pin "86") (pinfunction "PC09_86") (pintype "bidirectional"))
    )
    (net (code "65") (name "/PC10") (class "Default")
      (node (ref "R57") (pin "1") (pinfunction "1_1") (pintype "passive"))
      (node (ref "U2") (pin "90") (pinfunction "PC10_90") (pintype "bidirectional"))
    )
    (net (code "66") (name "/PC11") (class "Default")
      (node (ref "R58") (pin "1") (pinfunction "1_1") (pintype "passive"))
      (node (ref "U2") (pin "94") (pinfunction "PC11_94") (pintype "bidirectional"))
    )
    (net (code "67") (name "/PC12") (class "Default")
      (node (ref "R582") (pin "1") (pinfunction "1_1") (pintype "passive"))
      (node (ref "U2") (pin "17") (pinfunction "PC12_17") (pintype "bidirectional"))
    )
    (net (code "68") (name "/PC13") (class "Default")
      (node (ref "C218") (pin "2") (pinfunction "2_2") (pintype "passive"))
      (node (ref "R523") (pin "1") (pinfunction "1_1") (pintype "passive"))
      (node (ref "U2") (pin "19") (pinfunction "PC13_19") (pintype "bidirectional"))
    )
    (net (code "69") (name "/PC14") (class "Default")
      (node (ref "R583") (pin "1") (pinfunction "1_1") (pintype "passive"))
      (node (ref "U2") (pin "97") (pinfunction "PC14_97") (pintype "bidirectional"))
    )
    (net (code "70") (name "/PC15") (class "Default")
      (node (ref "C219") (pin "2") (pinfunction "2_2") (pintype "passive"))
      (node (ref "R524") (pin "1") (pinfunction "1_1") (pintype "passive"))
      (node (ref "U2") (pin "18") (pinfunction "PC15_18") (pintype "bidirectional"))
    )
    (net (code "71") (name "/PC16") (class "Default")
      (node (ref "R65") (pin "1") (pinfunction "1_1") (pintype "passive"))
      (node (ref "U2") (pin "100") (pinfunction "PC16_100") (pintype "bidirectional"))
    )
    (net (code "72") (name "/PC17") (class "Default")
      (node (ref "R67") (pin "1") (pinfunction "1_1") (pintype "passive"))
      (node (ref "U2") (pin "103") (pinfunction "PC17_103") (pintype "bidirectional"))
    )
    (net (code "73") (name "/PC18") (class "Default")
      (node (ref "R68") (pin "1") (pinfunction "1_1") (pintype "passive"))
      (node (ref "U2") (pin "111") (pinfunction "PC18_111") (pintype "bidirectional"))
    )
    (net (code "74") (name "/PC19") (class "Default")
      (node (ref "R69") (pin "1") (pinfunction "1_1") (pintype "passive"))
      (node (ref "U2") (pin "117") (pinfunction "PC19_117") (pintype "bidirectional"))
    )
    (net (code "75") (name "/PC20") (class "Default")
      (node (ref "R70") (pin "1") (pinfunction "1_1") (pintype "passive"))
      (node (ref "U2") (pin "120") (pinfunction "PC20_120") (pintype "bidirectional"))
    )
    (net (code "76") (name "/PC21") (class "Default")
      (node (ref "R71") (pin "1") (pinfunction "1_1") (pintype "passive"))
      (node (ref "U2") (pin "122") (pinfunction "PC21_122") (pintype "bidirectional"))
    )
    (net (code "77") (name "/PC22") (class "Default")
      (node (ref "R72") (pin "1") (pinfunction "1_1") (pintype "passive"))
      (node (ref "U2") (pin "124") (pinfunction "PC22_124") (pintype "bidirectional"))
    )
    (net (code "78") (name "/PC23") (class "Default")
      (node (ref "U2") (pin "127") (pinfunction "PC23_127") (pintype "bidirectional+no_connect"))
    )
    (net (code "79") (name "/PC24") (class "Default")
      (node (ref "R74") (pin "1") (pinfunction "1_1") (pintype "passive"))
      (node (ref "U2") (pin "130") (pinfunction "PC24_130") (pintype "bidirectional"))
    )
    (net (code "80") (name "/PC25") (class "Default")
      (node (ref "R525") (pin "1") (pinfunction "1_1") (pintype "passive"))
      (node (ref "U2") (pin "133") (pinfunction "PC25_133") (pintype "bidirectional"))
    )
    (net (code "81") (name "/PC26") (class "Default")
      (node (ref "R76") (pin "1") (pinfunction "1_1") (pintype "passive"))
      (node (ref "U2") (pin "13") (pinfunction "PC26_13") (pintype "bidirectional"))
    )
    (net (code "82") (name "/PC27") (class "Default")
      (node (ref "R77") (pin "1") (pinfunction "1_1") (pintype "passive"))
      (node (ref "U2") (pin "12") (pinfunction "PC27_12") (pintype "bidirectional"))
    )
    (net (code "83") (name "/PC28") (class "Default")
      (node (ref "R78") (pin "1") (pinfunction "1_1") (pintype "passive"))
      (node (ref "U2") (pin "76") (pinfunction "PC28_76") (pintype "bidirectional"))
    )
    (net (code "84") (name "/PC29") (class "Default")
      (node (ref "C208") (pin "2") (pinfunction "2_2") (pintype "passive"))
      (node (ref "R526") (pin "1") (pinfunction "1_1") (pintype "passive"))
      (node (ref "U2") (pin "16") (pinfunction "PC29_16") (pintype "bidirectional"))
    )
    (net (code "85") (name "/PC30") (class "Default")
      (node (ref "C209") (pin "2") (pinfunction "2_2") (pintype "passive"))
      (node (ref "R527") (pin "1") (pinfunction "1_1") (pintype "passive"))
      (node (ref "U2") (pin "15") (pinfunction "PC30_15") (pintype "bidirectional"))
    )
    (net (code "86") (name "/PC31") (class "Default")
      (node (ref "C210") (pin "2") (pinfunction "2_2") (pintype "passive"))
      (node (ref "R528") (pin "1") (pinfunction "1_1") (pintype "passive"))
      (node (ref "U2") (pin "14") (pinfunction "PC31_14") (pintype "bidirectional"))
    )
    (net (code "87") (name "/PD00") (class "Default")
      (node (ref "R56") (pin "2") (pinfunction "2_2") (pintype "passive"))
      (node (ref "U2") (pin "1") (pinfunction "PD00_1") (pintype "bidirectional"))
    )
    (net (code "88") (name "/PD01") (class "Default")
      (node (ref "R11") (pin "2") (pinfunction "2_2") (pintype "passive"))
      (node (ref "U2") (pin "132") (pinfunction "PD01_132") (pintype "bidirectional"))
    )
    (net (code "89") (name "/PD02") (class "Default")
      (node (ref "R26") (pin "2") (pinfunction "2_2") (pintype "passive"))
      (node (ref "U2") (pin "131") (pinfunction "PD02_131") (pintype "bidirectional"))
    )
    (net (code "90") (name "/PD03") (class "Default")
      (node (ref "R51") (pin "2") (pinfunction "2_2") (pintype "passive"))
      (node (ref "U2") (pin "128") (pinfunction "PD03_128") (pintype "bidirectional"))
    )
    (net (code "91") (name "/PD04") (class "Default")
      (node (ref "R52") (pin "2") (pinfunction "2_2") (pintype "passive"))
      (node (ref "U2") (pin "126") (pinfunction "PD04_126") (pintype "bidirectional"))
    )
    (net (code "92") (name "/PD05") (class "Default")
      (node (ref "R73") (pin "2") (pinfunction "2_2") (pintype "passive"))
      (node (ref "U2") (pin "125") (pinfunction "PD05_125") (pintype "bidirectional"))
    )
    (net (code "93") (name "/PD06") (class "Default")
      (node (ref "R75") (pin "2") (pinfunction "2_2") (pintype "passive"))
      (node (ref "U2") (pin "121") (pinfunction "PD06_121") (pintype "bidirectional"))
    )
    (net (code "94") (name "/PD07") (class "Default")
      (node (ref "R185") (pin "2") (pinfunction "2_2") (pintype "passive"))
      (node (ref "U2") (pin "119") (pinfunction "PD07_119") (pintype "bidirectional"))
    )
    (net (code "95") (name "/PD08") (class "Default")
      (node (ref "R186") (pin "2") (pinfunction "2_2") (pintype "passive"))
      (node (ref "U2") (pin "113") (pinfunction "PD08_113") (pintype "bidirectional"))
    )
    (net (code "96") (name "/PD09") (class "Default")
      (node (ref "R283") (pin "2") (pinfunction "2_2") (pintype "passive"))
      (node (ref "U2") (pin "110") (pinfunction "PD09_110") (pintype "bidirectional"))
    )
    (net (code "97") (name "/PD10") (class "Default")
      (node (ref "R284") (pin "2") (pinfunction "2_2") (pintype "passive"))
      (node (ref "U2") (pin "101") (pinfunction "PD10_101") (pintype "bidirectional"))
    )
    (net (code "98") (name "/PD11") (class "Default")
      (node (ref "R20") (pin "2") (pinfunction "2_2") (pintype "passive"))
      (node (ref "U2") (pin "98") (pinfunction "PD11_98") (pintype "bidirectional"))
    )
    (net (code "99") (name "/PD12") (class "Default")
      (node (ref "R22") (pin "2") (pinfunction "2_2") (pintype "passive"))
      (node (ref "U2") (pin "92") (pinfunction "PD12_92") (pintype "bidirectional"))
    )
    (net (code "100") (name "/PD13") (class "Default")
      (node (ref "R285") (pin "2") (pinfunction "2_2") (pintype "passive"))
      (node (ref "U2") (pin "88") (pinfunction "PD13_88") (pintype "bidirectional"))
    )
    (net (code "101") (name "/PD14") (class "Default")
      (node (ref "R286") (pin "2") (pinfunction "2_2") (pintype "passive"))
      (node (ref "U2") (pin "84") (pinfunction "PD14_84") (pintype "bidirectional"))
    )
    (net (code "102") (name "/PD15") (class "Default")
      (node (ref "R287") (pin "2") (pinfunction "2_2") (pintype "passive"))
      (node (ref "U2") (pin "106") (pinfunction "PD15_106") (pintype "bidirectional"))
    )
    (net (code "103") (name "/PD16") (class "Default")
      (node (ref "R288") (pin "2") (pinfunction "2_2") (pintype "passive"))
      (node (ref "U2") (pin "78") (pinfunction "PD16_78") (pintype "bidirectional"))
    )
    (net (code "104") (name "/PD17") (class "Default")
      (node (ref "R289") (pin "2") (pinfunction "2_2") (pintype "passive"))
      (node (ref "U2") (pin "74") (pinfunction "PD17_74") (pintype "bidirectional"))
    )
    (net (code "105") (name "/PD18") (class "Default")
      (node (ref "R290") (pin "2") (pinfunction "2_2") (pintype "passive"))
      (node (ref "U2") (pin "69") (pinfunction "PD18_69") (pintype "bidirectional"))
    )
    (net (code "106") (name "/PD19") (class "Default")
      (node (ref "R612") (pin "2") (pinfunction "2_2") (pintype "passive"))
      (node (ref "U2") (pin "67") (pinfunction "PD19_67") (pintype "bidirectional"))
    )
    (net (code "107") (name "/PD20") (class "Default")
      (node (ref "R28") (pin "2") (pinfunction "2_2") (pintype "passive"))
      (node (ref "U2") (pin "65") (pinfunction "PD20_65") (pintype "bidirectional"))
    )
    (net (code "108") (name "/PD21") (class "Default")
      (node (ref "R29") (pin "2") (pinfunction "2_2") (pintype "passive"))
      (node (ref "U2") (pin "63") (pinfunction "PD21_63") (pintype "bidirectional"))
    )
    (net (code "109") (name "/PD22") (class "Default")
      (node (ref "R31") (pin "2") (pinfunction "2_2") (pintype "passive"))
      (node (ref "U2") (pin "60") (pinfunction "PD22_60") (pintype "bidirectional"))
    )
    (net (code "110") (name "/PD23") (class "Default")
      (node (ref "R109") (pin "2") (pinfunction "2_2") (pintype "passive"))
      (node (ref "U2") (pin "57") (pinfunction "PD23_57") (pintype "bidirectional"))
    )
    (net (code "111") (name "/PD24") (class "Default")
      (node (ref "R110") (pin "2") (pinfunction "2_2") (pintype "passive"))
      (node (ref "U2") (pin "55") (pinfunction "PD24_55") (pintype "bidirectional"))
    )
    (net (code "112") (name "/PD25") (class "Default")
      (node (ref "R291") (pin "2") (pinfunction "2_2") (pintype "passive"))
      (node (ref "U2") (pin "52") (pinfunction "PD25_52") (pintype "bidirectional"))
    )
    (net (code "113") (name "/PD26") (class "Default")
      (node (ref "R292") (pin "2") (pinfunction "2_2") (pintype "passive"))
      (node (ref "U2") (pin "53") (pinfunction "PD26_53") (pintype "bidirectional"))
    )
    (net (code "114") (name "/PD27") (class "Default")
      (node (ref "R37") (pin "2") (pinfunction "2_2") (pintype "passive"))
      (node (ref "U2") (pin "47") (pinfunction "PD27_47") (pintype "bidirectional"))
    )
    (net (code "115") (name "/PD28") (class "Default")
      (node (ref "R39") (pin "2") (pinfunction "2_2") (pintype "passive"))
      (node (ref "U2") (pin "71") (pinfunction "PD28_71") (pintype "bidirectional"))
    )
    (net (code "116") (name "/PD29") (class "Default")
      (node (ref "R114") (pin "2") (pinfunction "2_2") (pintype "passive"))
      (node (ref "U2") (pin "108") (pinfunction "PD29_108") (pintype "bidirectional"))
    )
    (net (code "117") (name "/PD30") (class "Default")
      (node (ref "R116") (pin "2") (pinfunction "2_2") (pintype "passive"))
      (node (ref "U2") (pin "34") (pinfunction "PD30_34") (pintype "bidirectional"))
    )
    (net (code "118") (name "/PD31") (class "Default")
      (node (ref "R43") (pin "2") (pinfunction "2_2") (pintype "passive"))
      (node (ref "U2") (pin "2") (pinfunction "PD31_2") (pintype "bidirectional"))
    )
    (net (code "119") (name "/PE00") (class "Default")
      (node (ref "R595") (pin "2") (pinfunction "2_2") (pintype "passive"))
      (node (ref "U2") (pin "4") (pinfunction "PE00_4") (pintype "bidirectional"))
    )
    (net (code "120") (name "/PE01") (class "Default")
      (node (ref "R293") (pin "2") (pinfunction "2_2") (pintype "passive"))
      (node (ref "U2") (pin "6") (pinfunction "PE01_6") (pintype "bidirectional"))
    )
    (net (code "121") (name "/PE02") (class "Default")
      (node (ref "R294") (pin "2") (pinfunction "2_2") (pintype "passive"))
      (node (ref "U2") (pin "7") (pinfunction "PE02_7") (pintype "bidirectional"))
    )
    (net (code "122") (name "/PE03") (class "Default")
      (node (ref "C213") (pin "2") (pinfunction "2_2") (pintype "passive"))
      (node (ref "R123") (pin "2") (pinfunction "2_2") (pintype "passive"))
      (node (ref "U2") (pin "10") (pinfunction "PE03_10") (pintype "bidirectional"))
    )
    (net (code "123") (name "/PE04") (class "Default")
      (node (ref "R124") (pin "2") (pinfunction "2_2") (pintype "passive"))
      (node (ref "U2") (pin "27") (pinfunction "PE04_27") (pintype "bidirectional"))
    )
    (net (code "124") (name "/PE05") (class "Default")
      (node (ref "R616") (pin "2") (pinfunction "2_2") (pintype "passive"))
      (node (ref "U2") (pin "28") (pinfunction "PE05_28") (pintype "bidirectional"))
    )
    (net (code "125") (name "/nSTART") (class "Default")
      (node (ref "R525") (pin "2") (pinfunction "2_2") (pintype "passive"))
    )
    (net (code "126") (name "ADC_SWITCH") (class "Default")
      (node (ref "R522") (pin "1") (pinfunction "1_1") (pintype "passive"))
    )
    (net (code "127") (name "ADC_TEMP1") (class "Default")
      (node (ref "R100") (pin "2") (pinfunction "2_2") (pintype "passive"))
    )
    (net (code "128") (name "ADC_TEMP2") (class "Default")
      (node (ref "R104") (pin "2") (pinfunction "2_2") (pintype "passive"))
    )
    (net (code "129") (name "ADC_TEMP3") (class "Default")
      (node (ref "R297") (pin "1") (pinfunction "1_1") (pintype "passive"))
    )
    (net (code "130") (name "ADC_TEMP4") (class "Default")
      (node (ref "R520") (pin "1") (pinfunction "1_1") (pintype "passive"))
    )
    (net (code "131") (name "ADC_TEMP5") (class "Default")
      (node (ref "R524") (pin "2") (pinfunction "2_2") (pintype "passive"))
    )
    (net (code "132") (name "ADC_TEMP6") (class "Default")
      (node (ref "R523") (pin "2") (pinfunction "2_2") (pintype "passive"))
    )
    (net (code "133") (name "ADC_TEMP7") (class "Default")
      (node (ref "R521") (pin "1") (pinfunction "1_1") (pintype "passive"))
    )
    (net (code "134") (name "ADC_TEMP8") (class "Default")
      (node (ref "R526") (pin "2") (pinfunction "2_2") (pintype "passive"))
    )
    (net (code "135") (name "ADC_TEMP_SENSOR") (class "Default")
      (node (ref "R527") (pin "2") (pinfunction "2_2") (pintype "passive"))
    )
    (net (code "136") (name "ADC_eFUSEs") (class "Default")
      (node (ref "R123") (pin "1") (pinfunction "1_1") (pintype "passive"))
    )
    (net (code "137") (name "ADT2_USB_D_N") (class "Default")
      (node (ref "U2") (pin "136") (pinfunction "HSDM_136") (pintype "bidirectional"))
    )
    (net (code "138") (name "ADT2_USB_D_P") (class "Default")
      (node (ref "U2") (pin "137") (pinfunction "HSDP_137") (pintype "bidirectional"))
    )
    (net (code "139") (name "BMP390_INT") (class "Default")
      (node (ref "R11") (pin "1") (pinfunction "1_1") (pintype "passive"))
    )
    (net (code "140") (name "GND") (class "Default")
      (node (ref "C11") (pin "1") (pinfunction "1_1") (pintype "passive"))
      (node (ref "C12") (pin "1") (pinfunction "1_1") (pintype "passive"))
      (node (ref "C13") (pin "1") (pinfunction "1_1") (pintype "passive"))
      (node (ref "C14") (pin "1") (pinfunction "1_1") (pintype "passive"))
      (node (ref "C15") (pin "1") (pinfunction "1_1") (pintype "passive"))
      (node (ref "C16") (pin "1") (pinfunction "1_1") (pintype "passive"))
      (node (ref "C17") (pin "2") (pinfunction "2_2") (pintype "passive"))
      (node (ref "C18") (pin "2") (pinfunction "2_2") (pintype "passive"))
      (node (ref "C19") (pin "1") (pinfunction "1_1") (pintype "passive"))
      (node (ref "C20") (pin "1") (pinfunction "1_1") (pintype "passive"))
      (node (ref "C204") (pin "1") (pinfunction "1_1") (pintype "passive"))
      (node (ref "C205") (pin "1") (pinfunction "1_1") (pintype "passive"))
      (node (ref "C206") (pin "1") (pinfunction "1_1") (pintype "passive"))
      (node (ref "C207") (pin "1") (pinfunction "1_1") (pintype "passive"))
      (node (ref "C208") (pin "1") (pinfunction "1_1") (pintype "passive"))
      (node (ref "C209") (pin "1") (pinfunction "1_1") (pintype "passive"))
      (node (ref "C21") (pin "1") (pinfunction "1_1") (pintype "passive"))
      (node (ref "C210") (pin "1") (pinfunction "1_1") (pintype "passive"))
      (node (ref "C213") (pin "1") (pinfunction "1_1") (pintype "passive"))
      (node (ref "C214") (pin "1") (pinfunction "1_1") (pintype "passive"))
      (node (ref "C215") (pin "1") (pinfunction "1_1") (pintype "passive"))
      (node (ref "C216") (pin "1") (pinfunction "1_1") (pintype "passive"))
      (node (ref "C218") (pin "1") (pinfunction "1_1") (pintype "passive"))
      (node (ref "C219") (pin "1") (pinfunction "1_1") (pintype "passive"))
      (node (ref "C22") (pin "1") (pinfunction "1_1") (pintype "passive"))
      (node (ref "C23") (pin "1") (pinfunction "1_1") (pintype "passive"))
      (node (ref "C24") (pin "1") (pinfunction "1_1") (pintype "passive"))
      (node (ref "C25") (pin "1") (pinfunction "1_1") (pintype "passive"))
      (node (ref "C26") (pin "1") (pinfunction "1_1") (pintype "passive"))
      (node (ref "C27") (pin "1") (pinfunction "1_1") (pintype "passive"))
      (node (ref "C28") (pin "1") (pinfunction "1_1") (pintype "passive"))
      (node (ref "C29") (pin "1") (pinfunction "1_1") (pintype "passive"))
      (node (ref "C30") (pin "1") (pinfunction "1_1") (pintype "passive"))
      (node (ref "C31") (pin "1") (pinfunction "1_1") (pintype "passive"))
      (node (ref "C32") (pin "1") (pinfunction "1_1") (pintype "passive"))
      (node (ref "C33") (pin "1") (pinfunction "1_1") (pintype "passive"))
      (node (ref "C34") (pin "1") (pinfunction "1_1") (pintype "passive"))
      (node (ref "C35") (pin "1") (pinfunction "1_1") (pintype "passive"))
      (node (ref "J2") (pin "3") (pinfunction "3_3") (pintype "passive"))
      (node (ref "R83") (pin "1") (pinfunction "1_1") (pintype "passive"))
      (node (ref "U2") (pin "115") (pinfunction "GND_115") (pintype "power_in"))
      (node (ref "U2") (pin "135") (pinfunction "GND_135") (pintype "power_in"))
      (node (ref "U2") (pin "138") (pinfunction "GND_138") (pintype "power_in"))
      (node (ref "U2") (pin "44") (pinfunction "GND_44") (pintype "power_in"))
      (node (ref "U2") (pin "61") (pinfunction "GND_61") (pintype "power_in"))
      (node (ref "U2") (pin "8") (pinfunction "ADVREFN_8") (pintype "power_in"))
      (node (ref "U2") (pin "95") (pinfunction "GND_95") (pintype "power_in"))
      (node (ref "XC2") (pin "2") (pinfunction "2_2") (pintype "passive"))
      (node (ref "XC2") (pin "4") (pinfunction "4_4") (pintype "passive"))
    )
    (net (code "141") (name "HEATER_PWM_1") (class "Default")
      (node (ref "R36") (pin "2") (pinfunction "2_2") (pintype "passive"))
    )
    (net (code "142") (name "HEATER_PWM_2") (class "Default")
      (node (ref "R9") (pin "2") (pinfunction "2_2") (pintype "passive"))
    )
    (net (code "143") (name "HEATER_PWM_3") (class "Default")
      (node (ref "R10") (pin "2") (pinfunction "2_2") (pintype "passive"))
    )
    (net (code "144") (name "HEATER_PWM_4") (class "Default")
      (node (ref "R35") (pin "2") (pinfunction "2_2") (pintype "passive"))
    )
    (net (code "145") (name "LASER_ADC_1") (class "Default")
      (node (ref "R528") (pin "2") (pinfunction "2_2") (pintype "passive"))
    )
    (net (code "146") (name "LASER_ADC_2") (class "Default")
      (node (ref "R627") (pin "2") (pinfunction "2_2") (pintype "passive"))
    )
    (net (code "147") (name "LASER_CHOSE") (class "Default")
      (node (ref "R595") (pin "1") (pinfunction "1_1") (pintype "passive"))
    )
    (net (code "148") (name "LASER_DAC_LATCH") (class "Default")
      (node (ref "R65") (pin "2") (pinfunction "2_2") (pintype "passive"))
    )
    (net (code "149") (name "LASER_SPI_nCS1") (class "Default")
      (node (ref "R42") (pin "2") (pinfunction "2_2") (pintype "passive"))
    )
    (net (code "150") (name "LASER_SW_EXT_CS") (class "Default")
      (node (ref "R54") (pin "2") (pinfunction "2_2") (pintype "passive"))
    )
    (net (code "151") (name "LASER_SW_INT_CS") (class "Default")
      (node (ref "R53") (pin "2") (pinfunction "2_2") (pintype "passive"))
    )
    (net (code "152") (name "LSM6D_INT1") (class "Default")
      (node (ref "R71") (pin "2") (pinfunction "2_2") (pintype "passive"))
    )
    (net (code "153") (name "MCU_CAN1_RX") (class "Default")
      (node (ref "R582") (pin "2") (pinfunction "2_2") (pintype "passive"))
    )
    (net (code "154") (name "MCU_CAN1_TX") (class "Default")
      (node (ref "R583") (pin "2") (pinfunction "2_2") (pintype "passive"))
    )
    (net (code "155") (name "MCU_CONSOLE_RX") (class "Default")
      (node (ref "R291") (pin "1") (pinfunction "1_1") (pintype "passive"))
    )
    (net (code "156") (name "MCU_CONSOLE_TX") (class "Default")
      (node (ref "R292") (pin "1") (pinfunction "1_1") (pintype "passive"))
    )
    (net (code "157") (name "MCU_FRAM_nCS") (class "Default")
      (node (ref "R612") (pin "1") (pinfunction "1_1") (pintype "passive"))
    )
    (net (code "158") (name "MCU_HD4_I2C2_SCL") (class "Default")
      (node (ref "R39") (pin "1") (pinfunction "1_1") (pintype "passive"))
    )
    (net (code "159") (name "MCU_HD4_I2C2_SDA") (class "Default")
      (node (ref "R37") (pin "1") (pinfunction "1_1") (pintype "passive"))
    )
    (net (code "160") (name "MCU_HD4_I2C_EN") (class "Default")
      (node (ref "R67") (pin "2") (pinfunction "2_2") (pintype "passive"))
    )
    (net (code "161") (name "MCU_I2C0_SCL") (class "Default")
      (node (ref "R14") (pin "2") (pinfunction "2_2") (pintype "passive"))
    )
    (net (code "162") (name "MCU_I2C0_SDA") (class "Default")
      (node (ref "R13") (pin "2") (pinfunction "2_2") (pintype "passive"))
    )
    (net (code "163") (name "MCU_MRAM_QSPI_CLK") (class "Default")
      (node (ref "R24") (pin "2") (pinfunction "2_2") (pintype "passive"))
    )
    (net (code "164") (name "MCU_MRAM_QSPI_IO0") (class "Default")
      (node (ref "R23") (pin "2") (pinfunction "2_2") (pintype "passive"))
    )
    (net (code "165") (name "MCU_MRAM_QSPI_IO1") (class "Default")
      (node (ref "R21") (pin "2") (pinfunction "2_2") (pintype "passive"))
    )
    (net (code "166") (name "MCU_MRAM_QSPI_IO2") (class "Default")
      (node (ref "R27") (pin "2") (pinfunction "2_2") (pintype "passive"))
    )
    (net (code "167") (name "MCU_MRAM_QSPI_IO3") (class "Default")
      (node (ref "R43") (pin "1") (pinfunction "1_1") (pintype "passive"))
    )
    (net (code "168") (name "MCU_PRAM_SPI1_nCS") (class "Default")
      (node (ref "R78") (pin "2") (pinfunction "2_2") (pintype "passive"))
    )
    (net (code "169") (name "MCU_PRAM_SW_nEN") (class "Default")
      (node (ref "R286") (pin "1") (pinfunction "1_1") (pintype "passive"))
    )
    (net (code "170") (name "MCU_RAM_QSPI_nCS") (class "Default")
      (node (ref "R19") (pin "2") (pinfunction "2_2") (pintype "passive"))
    )
    (net (code "171") (name "MCU_RTC_CLKOUT") (class "Default")
      (node (ref "R49") (pin "2") (pinfunction "2_2") (pintype "passive"))
    )
    (net (code "172") (name "MCU_RTC_INT") (class "Default")
      (node (ref "R50") (pin "2") (pinfunction "2_2") (pintype "passive"))
    )
    (net (code "173") (name "MCU_SENSOR1_nIRQ") (class "Default")
      (node (ref "R109") (pin "1") (pinfunction "1_1") (pintype "passive"))
    )
    (net (code "174") (name "MCU_SENSOR2_nIRQ") (class "Default")
      (node (ref "R110") (pin "1") (pinfunction "1_1") (pintype "passive"))
    )
    (net (code "175") (name "MCU_SENSOR3_nIRQ") (class "Default")
      (node (ref "R114") (pin "1") (pinfunction "1_1") (pintype "passive"))
    )
    (net (code "176") (name "MCU_SENSOR4_nIRQ") (class "Default")
      (node (ref "R116") (pin "1") (pinfunction "1_1") (pintype "passive"))
    )
    (net (code "177") (name "MCU_SOL_1_IN1") (class "Default")
      (node (ref "R12") (pin "2") (pinfunction "2_2") (pintype "passive"))
    )
    (net (code "178") (name "MCU_SOL_1_IN2") (class "Default")
      (node (ref "R69") (pin "2") (pinfunction "2_2") (pintype "passive"))
    )
    (net (code "179") (name "MCU_SOL_2_IN1") (class "Default")
      (node (ref "R290") (pin "1") (pinfunction "1_1") (pintype "passive"))
    )
    (net (code "180") (name "MCU_SOL_2_IN2") (class "Default")
      (node (ref "R616") (pin "1") (pinfunction "1_1") (pintype "passive"))
    )
    (net (code "181") (name "MCU_SOL_3_IN1") (class "Default")
      (node (ref "R32") (pin "2") (pinfunction "2_2") (pintype "passive"))
    )
    (net (code "182") (name "MCU_SOL_3_IN2") (class "Default")
      (node (ref "R30") (pin "2") (pinfunction "2_2") (pintype "passive"))
    )
    (net (code "183") (name "MCU_SOL_4_IN1") (class "Default")
      (node (ref "R34") (pin "2") (pinfunction "2_2") (pintype "passive"))
    )
    (net (code "184") (name "MCU_SOL_4_IN2") (class "Default")
      (node (ref "R33") (pin "2") (pinfunction "2_2") (pintype "passive"))
    )
    (net (code "185") (name "MCU_SOM_GPIO_A") (class "Default")
      (node (ref "R283") (pin "1") (pinfunction "1_1") (pintype "passive"))
    )
    (net (code "186") (name "MCU_SOM_GPIO_B") (class "Default")
      (node (ref "R284") (pin "1") (pinfunction "1_1") (pintype "passive"))
    )
    (net (code "187") (name "MCU_SPI0_MISO") (class "Default")
      (node (ref "R28") (pin "1") (pinfunction "1_1") (pintype "passive"))
      (node (ref "R80") (pin "1") (pinfunction "1_1") (pintype "passive"))
    )
    (net (code "188") (name "MCU_SPI0_MOSI") (class "Default")
      (node (ref "R29") (pin "1") (pinfunction "1_1") (pintype "passive"))
    )
    (net (code "189") (name "MCU_SPI0_SCK") (class "Default")
      (node (ref "R31") (pin "1") (pinfunction "1_1") (pintype "passive"))
    )
    (net (code "190") (name "MCU_SPI1_MISO") (class "Default")
      (node (ref "R76") (pin "2") (pinfunction "2_2") (pintype "passive"))
    )
    (net (code "191") (name "MCU_SPI1_MOSI") (class "Default")
      (node (ref "R77") (pin "2") (pinfunction "2_2") (pintype "passive"))
    )
    (net (code "192") (name "MCU_SPI1_SCK") (class "Default")
      (node (ref "R74") (pin "2") (pinfunction "2_2") (pintype "passive"))
    )
    (net (code "193") (name "MCU_UART0_RX_SOM_TX") (class "Default")
      (node (ref "R17") (pin "2") (pinfunction "2_2") (pintype "passive"))
    )
    (net (code "194") (name "MCU_UART0_TX_SOM_RX") (class "Default")
      (node (ref "R18") (pin "2") (pinfunction "2_2") (pintype "passive"))
    )
    (net (code "195") (name "MCU_UART1_RX_SOM_TX") (class "Default")
      (node (ref "R15") (pin "2") (pinfunction "2_2") (pintype "passive"))
    )
    (net (code "196") (name "MCU_UART1_TX_SOM_RX") (class "Default")
      (node (ref "R16") (pin "2") (pinfunction "2_2") (pintype "passive"))
    )
    (net (code "197") (name "MCU_USART_RXD2") (class "Default")
      (node (ref "R287") (pin "1") (pinfunction "1_1") (pintype "passive"))
    )
    (net (code "198") (name "MCU_USART_SCK2") (class "Default")
      (node (ref "R289") (pin "1") (pinfunction "1_1") (pintype "passive"))
    )
    (net (code "199") (name "MCU_USART_TXD2") (class "Default")
      (node (ref "R288") (pin "1") (pinfunction "1_1") (pintype "passive"))
    )
    (net (code "200") (name "MCU_WD_DONE") (class "Default")
      (node (ref "R293") (pin "1") (pinfunction "1_1") (pintype "passive"))
    )
    (net (code "201") (name "MCU_WD_WAKE") (class "Default")
      (node (ref "R294") (pin "1") (pinfunction "1_1") (pintype "passive"))
    )
    (net (code "202") (name "MCU_WD_nRESET") (class "Default")
      (node (ref "R45") (pin "2") (pinfunction "2_2") (pintype "passive"))
    )
    (net (code "203") (name "Net-(C11-Pad2)") (class "Default")
      (node (ref "C11") (pin "2") (pinfunction "2_2") (pintype "passive"))
      (node (ref "R44") (pin "1") (pinfunction "1_1") (pintype "passive"))
      (node (ref "R45") (pin "1") (pinfunction "1_1") (pintype "passive"))
      (node (ref "R46") (pin "2") (pinfunction "2_2") (pintype "passive"))
    )
    (net (code "204") (name "Net-(D33-K)") (class "Default")
      (node (ref "D33") (pin "1") (pinfunction "K_1") (pintype "passive"))
      (node (ref "R166") (pin "2") (pinfunction "2_2") (pintype "passive"))
    )
    (net (code "205") (name "Net-(U2-VBG)") (class "Default")
      (node (ref "C14") (pin "2") (pinfunction "2_2") (pintype "passive"))
      (node (ref "R83") (pin "2") (pinfunction "2_2") (pintype "passive"))
      (node (ref "U2") (pin "140") (pinfunction "VBG_140") (pintype "power_in"))
    )
    (net (code "206") (name "PHOTO_ADC_CONV") (class "Default")
      (node (ref "R25") (pin "2") (pinfunction "2_2") (pintype "passive"))
    )
    (net (code "207") (name "PHOTO_ADC_CS") (class "Default")
      (node (ref "R56") (pin "1") (pinfunction "1_1") (pintype "passive"))
    )
    (net (code "208") (name "PHOTO_ADC_EOC") (class "Default")
      (node (ref "R99") (pin "2") (pinfunction "2_2") (pintype "passive"))
    )
    (net (code "209") (name "PHOTO_CHOSE") (class "Default")
      (node (ref "R124") (pin "1") (pinfunction "1_1") (pintype "passive"))
    )
    (net (code "210") (name "PHOTO_SPI0_nCS2") (class "Default")
      (node (ref "R22") (pin "1") (pinfunction "1_1") (pintype "passive"))
    )
    (net (code "211") (name "POW_ONOFF_5V") (class "Default")
      (node (ref "R51") (pin "1") (pinfunction "1_1") (pintype "passive"))
    )
    (net (code "212") (name "POW_ONOFF_HD4") (class "Default")
      (node (ref "R73") (pin "1") (pinfunction "1_1") (pintype "passive"))
    )
    (net (code "213") (name "POW_ONOFF_Heater") (class "Default")
      (node (ref "R632") (pin "1") (pinfunction "1_1") (pintype "passive"))
    )
    (net (code "214") (name "POW_ONOFF_Laser") (class "Default")
      (node (ref "R186") (pin "1") (pinfunction "1_1") (pintype "passive"))
    )
    (net (code "215") (name "POW_ONOFF_Photo") (class "Default")
      (node (ref "R185") (pin "1") (pinfunction "1_1") (pintype "passive"))
    )
    (net (code "216") (name "POW_ONOFF_SOM") (class "Default")
      (node (ref "R26") (pin "1") (pinfunction "1_1") (pintype "passive"))
    )
    (net (code "217") (name "POW_ONOFF_Solenoid") (class "Default")
      (node (ref "R75") (pin "1") (pinfunction "1_1") (pintype "passive"))
    )
    (net (code "218") (name "POW_ONOFF_TEC") (class "Default")
      (node (ref "R52") (pin "1") (pinfunction "1_1") (pintype "passive"))
    )
    (net (code "219") (name "SENSOR1_EN") (class "Default")
      (node (ref "R55") (pin "2") (pinfunction "2_2") (pintype "passive"))
    )
    (net (code "220") (name "SENSOR2_EN") (class "Default")
      (node (ref "R57") (pin "2") (pinfunction "2_2") (pintype "passive"))
    )
    (net (code "221") (name "SENSOR3_EN") (class "Default")
      (node (ref "R38") (pin "2") (pinfunction "2_2") (pintype "passive"))
    )
    (net (code "222") (name "SENSOR4_EN") (class "Default")
      (node (ref "R40") (pin "2") (pinfunction "2_2") (pintype "passive"))
    )
    (net (code "223") (name "SENSOR5_EN") (class "Default")
      (node (ref "R58") (pin "2") (pinfunction "2_2") (pintype "passive"))
    )
    (net (code "224") (name "SENSOR_I2C1_SCL") (class "Default")
      (node (ref "R62") (pin "1") (pinfunction "1_1") (pintype "passive"))
    )
    (net (code "225") (name "SENSOR_I2C1_SDA") (class "Default")
      (node (ref "R59") (pin "1") (pinfunction "1_1") (pintype "passive"))
    )
    (net (code "226") (name "TEC_SWEN_1") (class "Default")
      (node (ref "R41") (pin "2") (pinfunction "2_2") (pintype "passive"))
    )
    (net (code "227") (name "TEC_SWEN_2") (class "Default")
      (node (ref "R285") (pin "1") (pinfunction "1_1") (pintype "passive"))
    )
    (net (code "228") (name "TEC_SWEN_3") (class "Default")
      (node (ref "R47") (pin "2") (pinfunction "2_2") (pintype "passive"))
    )
    (net (code "229") (name "TEC_SWEN_4") (class "Default")
      (node (ref "R48") (pin "2") (pinfunction "2_2") (pintype "passive"))
    )
    (net (code "230") (name "TEC_nCS_1") (class "Default")
      (node (ref "R68") (pin "2") (pinfunction "2_2") (pintype "passive"))
    )
    (net (code "231") (name "TEC_nCS_2") (class "Default")
      (node (ref "R70") (pin "2") (pinfunction "2_2") (pintype "passive"))
    )
    (net (code "232") (name "TEC_nCS_3") (class "Default")
      (node (ref "R72") (pin "2") (pinfunction "2_2") (pintype "passive"))
    )
    (net (code "233") (name "TEC_nCS_4") (class "Default")
      (node (ref "R20") (pin "1") (pinfunction "1_1") (pintype "passive"))
    )
    (net (code "234") (name "unconnected-(J2-Pad1)") (class "Default")
      (node (ref "J2") (pin "1") (pinfunction "1_1") (pintype "passive"))
    )
    (net (code "235") (name "unconnected-(J2-Pad7)") (class "Default")
      (node (ref "J2") (pin "7") (pinfunction "7_7") (pintype "passive"))
    )
  )
)
